# schema.net
KiCad netlist of a schematic drawn in EAGLE
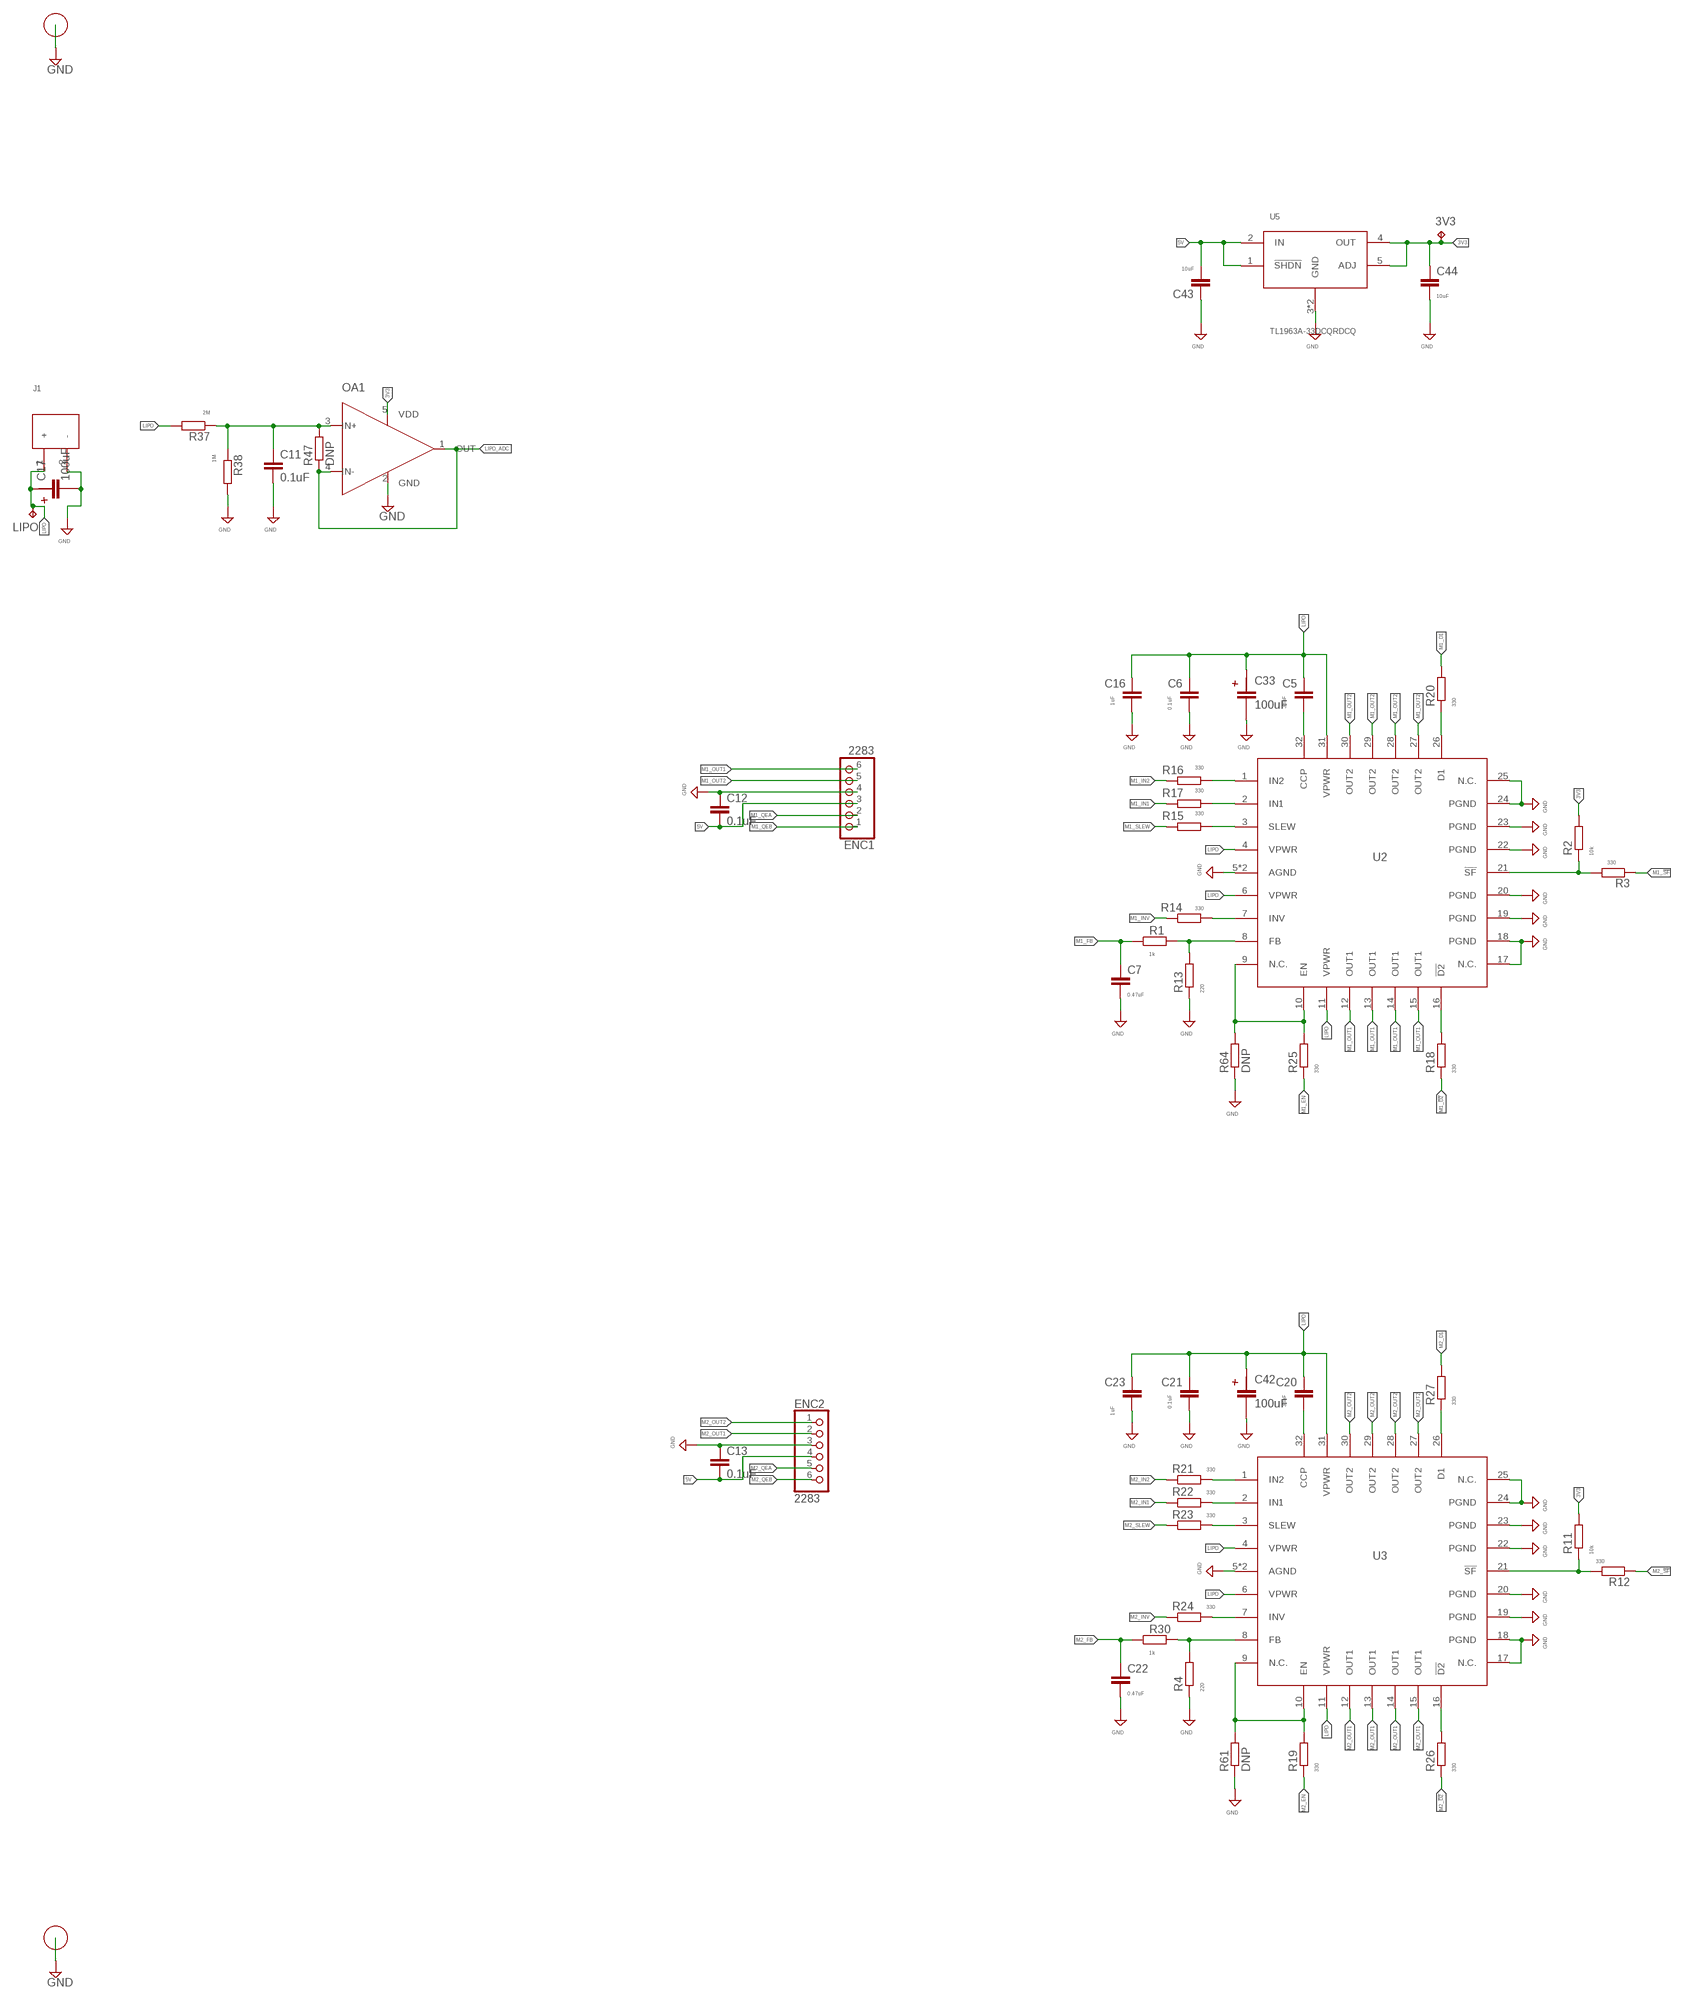
[diagram p0: schematic, sheet 1, part 1 of 2]
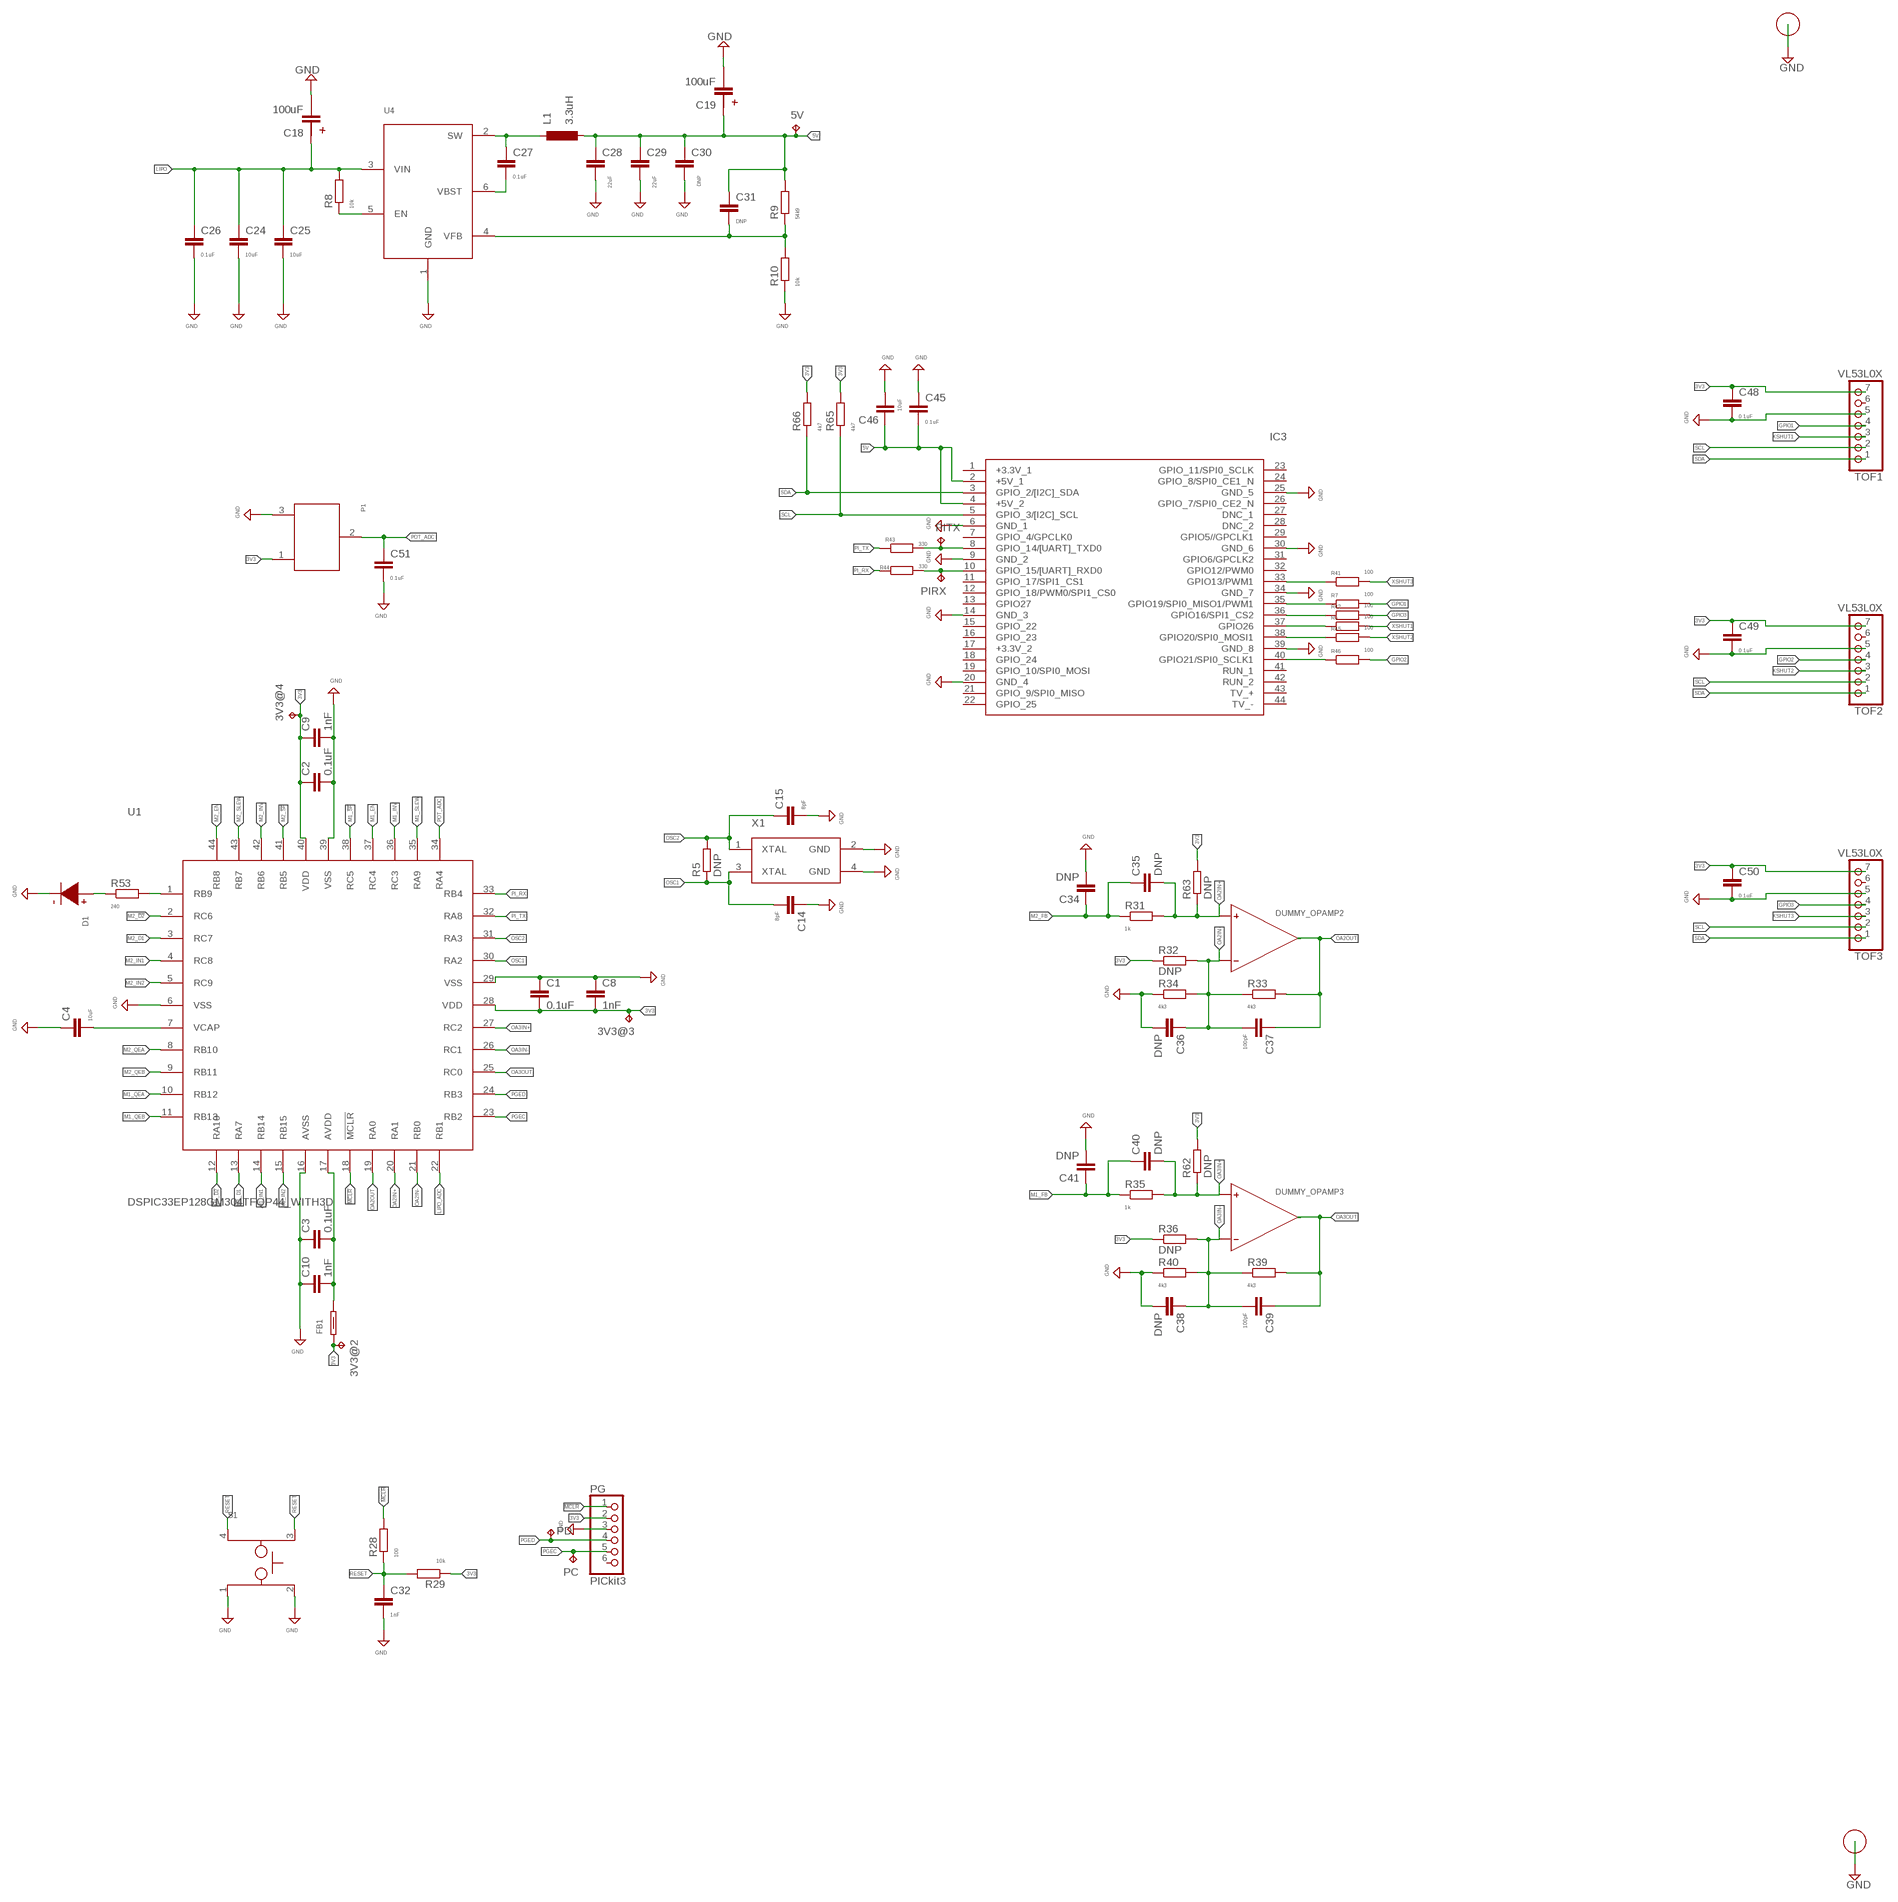
[diagram p1: schematic, sheet 1, part 2 of 2]

(export (version "E")
  (design (tool "Eeschema 10.0.6"))
  (components
    (comp (ref "3V3")
      (value "TPB1,27")
      (footprint "eagle-import:B1,27")
      (libsource (lib "eagle-import") (part "TPB1,27"))
    )
    (comp (ref "3V3@2")
      (value "TPB1,27")
      (footprint "eagle-import:B1,27")
      (libsource (lib "eagle-import") (part "TPB1,27"))
    )
    (comp (ref "3V3@3")
      (value "TPB1,27")
      (footprint "eagle-import:B1,27")
      (libsource (lib "eagle-import") (part "TPB1,27"))
    )
    (comp (ref "3V3@4")
      (value "TPB1,27")
      (footprint "eagle-import:B1,27")
      (libsource (lib "eagle-import") (part "TPB1,27"))
    )
    (comp (ref "5V")
      (value "TPB1,27")
      (footprint "eagle-import:B1,27")
      (libsource (lib "eagle-import") (part "TPB1,27"))
    )
    (comp (ref "C1")
      (value "0.1uF")
      (footprint "eagle-import:C0402K")
      (fields (field (name "MANUFACTURER_PART_NUMBER") "CC0402KRX7R7BB104"))
      (libsource (lib "eagle-import") (part "C-EUC0402K"))
    )
    (comp (ref "C2")
      (value "0.1uF")
      (footprint "eagle-import:C0402K")
      (fields (field (name "MANUFACTURER_PART_NUMBER") "CC0402KRX7R7BB104"))
      (libsource (lib "eagle-import") (part "C-EUC0402K"))
    )
    (comp (ref "C3")
      (value "0.1uF")
      (footprint "eagle-import:C0402K")
      (fields (field (name "MANUFACTURER_PART_NUMBER") "CC0402KRX7R7BB104"))
      (libsource (lib "eagle-import") (part "C-EUC0402K"))
    )
    (comp (ref "C4")
      (value "10uF")
      (footprint "eagle-import:C1210K")
      (fields (field (name "MANUFACTURER_PART_NUMBER") "TAJB106K016TNJ"))
      (libsource (lib "eagle-import") (part "C-EUC1210K"))
    )
    (comp (ref "C5")
      (value "33nF")
      (footprint "eagle-import:C0603K")
      (fields (field (name "MANUFACTURER_PART_NUMBER") "CC0603KRX7R9BB333"))
      (libsource (lib "eagle-import") (part "C-EUC0603K"))
    )
    (comp (ref "C6")
      (value "0.1uF")
      (footprint "eagle-import:C0603K")
      (fields (field (name "MANUFACTURER_PART_NUMBER") "CC0603KRX7R9BB104"))
      (libsource (lib "eagle-import") (part "C-EUC0603K"))
    )
    (comp (ref "C7")
      (value "0.47uF")
      (footprint "eagle-import:C0603K")
      (fields (field (name "MANUFACTURER_PART_NUMBER") "TMK107B7474KA-TR"))
      (libsource (lib "eagle-import") (part "C-EUC0603K"))
    )
    (comp (ref "C8")
      (value "1nF")
      (footprint "eagle-import:C0402K")
      (fields (field (name "MANUFACTURER_PART_NUMBER") "AC0402KRX7R7BB102"))
      (libsource (lib "eagle-import") (part "C-EUC0402K"))
    )
    (comp (ref "C9")
      (value "1nF")
      (footprint "eagle-import:C0402K")
      (fields (field (name "MANUFACTURER_PART_NUMBER") "AC0402KRX7R7BB102"))
      (libsource (lib "eagle-import") (part "C-EUC0402K"))
    )
    (comp (ref "C10")
      (value "1nF")
      (footprint "eagle-import:C0402K")
      (fields (field (name "MANUFACTURER_PART_NUMBER") "AC0402KRX7R7BB102"))
      (libsource (lib "eagle-import") (part "C-EUC0402K"))
    )
    (comp (ref "C11")
      (value "0.1uF")
      (footprint "eagle-import:C0603K")
      (fields (field (name "MANUFACTURER_PART_NUMBER") "CC0603KRX7R9BB104"))
      (libsource (lib "eagle-import") (part "C-EUC0603K"))
    )
    (comp (ref "C12")
      (value "0.1uF")
      (footprint "eagle-import:C0603K")
      (fields (field (name "MANUFACTURER_PART_NUMBER") "CC0603KRX7R9BB104"))
      (libsource (lib "eagle-import") (part "C-EUC0603K"))
    )
    (comp (ref "C13")
      (value "0.1uF")
      (footprint "eagle-import:C0603K")
      (fields (field (name "MANUFACTURER_PART_NUMBER") "CC0603KRX7R9BB104"))
      (libsource (lib "eagle-import") (part "C-EUC0603K"))
    )
    (comp (ref "C14")
      (value "8pF")
      (footprint "eagle-import:C0402K")
      (fields (field (name "MANUFACTURER_PART_NUMBER") "GCM1555C1H8R0DA16D"))
      (libsource (lib "eagle-import") (part "C-EUC0402K"))
    )
    (comp (ref "C15")
      (value "8pF")
      (footprint "eagle-import:C0402K")
      (fields (field (name "MANUFACTURER_PART_NUMBER") "GCM1555C1H8R0DA16D"))
      (libsource (lib "eagle-import") (part "C-EUC0402K"))
    )
    (comp (ref "C16")
      (value "1uF")
      (footprint "eagle-import:C0603K")
      (fields (field (name "MANUFACTURER_PART_NUMBER") "UMK107AB7105KA-T"))
      (libsource (lib "eagle-import") (part "C-EUC0603K"))
    )
    (comp (ref "C17")
      (value "100uF")
      (footprint "eagle-import:CAPMP7141X430")
      (fields (field (name "MANUFACTURER_PART_NUMBER") "T491X107M025AT"))
      (libsource (lib "eagle-import") (part "TANTALUM_2917CASE_X"))
    )
    (comp (ref "C18")
      (value "100uF")
      (footprint "eagle-import:CAPAE660X770")
      (fields (field (name "MANUFACTURER_PART_NUMBER") "865080545012"))
      (libsource (lib "eagle-import") (part "WURTH_CAPWE"))
    )
    (comp (ref "C19")
      (value "100uF")
      (footprint "eagle-import:CAPAE660X770")
      (fields (field (name "MANUFACTURER_PART_NUMBER") "865080545012"))
      (libsource (lib "eagle-import") (part "WURTH_CAPWE"))
    )
    (comp (ref "C20")
      (value "33nF")
      (footprint "eagle-import:C0603K")
      (fields (field (name "MANUFACTURER_PART_NUMBER") "CC0603KRX7R9BB333"))
      (libsource (lib "eagle-import") (part "C-EUC0603K"))
    )
    (comp (ref "C21")
      (value "0.1uF")
      (footprint "eagle-import:C0603K")
      (fields (field (name "MANUFACTURER_PART_NUMBER") "CC0603KRX7R9BB104"))
      (libsource (lib "eagle-import") (part "C-EUC0603K"))
    )
    (comp (ref "C22")
      (value "0.47uF")
      (footprint "eagle-import:C0603K")
      (fields (field (name "MANUFACTURER_PART_NUMBER") "TMK107B7474KA-TR"))
      (libsource (lib "eagle-import") (part "C-EUC0603K"))
    )
    (comp (ref "C23")
      (value "1uF")
      (footprint "eagle-import:C0603K")
      (fields (field (name "MANUFACTURER_PART_NUMBER") "UMK107AB7105KA-T"))
      (libsource (lib "eagle-import") (part "C-EUC0603K"))
    )
    (comp (ref "C24")
      (value "10uF")
      (footprint "eagle-import:C1206K")
      (fields (field (name "MANUFACTURER_PART_NUMBER") "GMK316AB7106KL-TR"))
      (libsource (lib "eagle-import") (part "C-EUC1206K"))
    )
    (comp (ref "C25")
      (value "10uF")
      (footprint "eagle-import:C1206K")
      (fields (field (name "MANUFACTURER_PART_NUMBER") "GMK316AB7106KL-TR"))
      (libsource (lib "eagle-import") (part "C-EUC1206K"))
    )
    (comp (ref "C26")
      (value "0.1uF")
      (footprint "eagle-import:C0603K")
      (fields (field (name "MANUFACTURER_PART_NUMBER") "CC0603KRX7R9BB104"))
      (libsource (lib "eagle-import") (part "C-EUC0603K"))
    )
    (comp (ref "C27")
      (value "0.1uF")
      (footprint "eagle-import:C0603K")
      (fields (field (name "MANUFACTURER_PART_NUMBER") "CC0603KRX7R9BB104"))
      (libsource (lib "eagle-import") (part "C-EUC0603K"))
    )
    (comp (ref "C28")
      (value "22uF")
      (footprint "eagle-import:C1206")
      (fields (field (name "MANUFACTURER_PART_NUMBER") "EMK316BB7226ML-T"))
      (libsource (lib "eagle-import") (part "C-EUC1206"))
    )
    (comp (ref "C29")
      (value "22uF")
      (footprint "eagle-import:C1206")
      (fields (field (name "MANUFACTURER_PART_NUMBER") "EMK316BB7226ML-T"))
      (libsource (lib "eagle-import") (part "C-EUC1206"))
    )
    (comp (ref "C30")
      (value "DNP")
      (footprint "eagle-import:C1206")
      (libsource (lib "eagle-import") (part "C-EUC1206"))
    )
    (comp (ref "C31")
      (value "DNP")
      (footprint "eagle-import:C0603K")
      (libsource (lib "eagle-import") (part "C-EUC0603K"))
    )
    (comp (ref "C32")
      (value "1nF")
      (footprint "eagle-import:C0603K")
      (fields (field (name "MANUFACTURER_PART_NUMBER") "885012206083"))
      (libsource (lib "eagle-import") (part "C-EUC0603K"))
    )
    (comp (ref "C33")
      (value "100uF")
      (footprint "eagle-import:CAPAE660X800")
      (fields (field (name "MANUFACTURER_PART_NUMBER") "EEH-ZA1E101XV"))
      (libsource (lib "eagle-import") (part "EEH-ZA1E101XVCAP_D8"))
    )
    (comp (ref "C34")
      (value "DNP")
      (footprint "eagle-import:C0603K")
      (libsource (lib "eagle-import") (part "C-EUC0603K"))
    )
    (comp (ref "C35")
      (value "DNP")
      (footprint "eagle-import:C0603K")
      (libsource (lib "eagle-import") (part "C-EUC0603K"))
    )
    (comp (ref "C36")
      (value "DNP")
      (footprint "eagle-import:C0603K")
      (libsource (lib "eagle-import") (part "C-EUC0603K"))
    )
    (comp (ref "C37")
      (value "100pF")
      (footprint "eagle-import:C0603K")
      (fields (field (name "MANUFACTURER_PART_NUMBER") "885342206001"))
      (libsource (lib "eagle-import") (part "C-EUC0603K"))
    )
    (comp (ref "C38")
      (value "DNP")
      (footprint "eagle-import:C0603K")
      (libsource (lib "eagle-import") (part "C-EUC0603K"))
    )
    (comp (ref "C39")
      (value "100pF")
      (footprint "eagle-import:C0603K")
      (fields (field (name "MANUFACTURER_PART_NUMBER") "885342206001"))
      (libsource (lib "eagle-import") (part "C-EUC0603K"))
    )
    (comp (ref "C40")
      (value "DNP")
      (footprint "eagle-import:C0603K")
      (libsource (lib "eagle-import") (part "C-EUC0603K"))
    )
    (comp (ref "C41")
      (value "DNP")
      (footprint "eagle-import:C0603K")
      (libsource (lib "eagle-import") (part "C-EUC0603K"))
    )
    (comp (ref "C42")
      (value "100uF")
      (footprint "eagle-import:CAPAE660X800")
      (fields (field (name "MANUFACTURER_PART_NUMBER") "EEH-ZA1E101XV"))
      (libsource (lib "eagle-import") (part "EEH-ZA1E101XVCAP_D8"))
    )
    (comp (ref "C43")
      (value "10uF")
      (footprint "eagle-import:C1210K")
      (fields (field (name "MANUFACTURER_PART_NUMBER") "GRM32DR71E106MA12L"))
      (libsource (lib "eagle-import") (part "C-EUC1210K"))
    )
    (comp (ref "C44")
      (value "10uF")
      (footprint "eagle-import:C1210K")
      (fields (field (name "MANUFACTURER_PART_NUMBER") "GRM32DR71E106MA12L"))
      (libsource (lib "eagle-import") (part "C-EUC1210K"))
    )
    (comp (ref "C45")
      (value "0.1uF")
      (footprint "eagle-import:C0603K")
      (fields (field (name "MANUFACTURER_PART_NUMBER") "CC0603KRX7R9BB104"))
      (libsource (lib "eagle-import") (part "C-EUC0603K"))
    )
    (comp (ref "C46")
      (value "10uF")
      (footprint "eagle-import:C1210K")
      (fields (field (name "MANUFACTURER_PART_NUMBER") "TAJB106K016TNJ"))
      (libsource (lib "eagle-import") (part "C-EUC1210K"))
    )
    (comp (ref "C48")
      (value "0.1uF")
      (footprint "eagle-import:C0603K")
      (fields (field (name "MANUFACTURER_PART_NUMBER") "CC0603KRX7R9BB104"))
      (libsource (lib "eagle-import") (part "C-EUC0603K"))
    )
    (comp (ref "C49")
      (value "0.1uF")
      (footprint "eagle-import:C0603K")
      (fields (field (name "MANUFACTURER_PART_NUMBER") "CC0603KRX7R9BB104"))
      (libsource (lib "eagle-import") (part "C-EUC0603K"))
    )
    (comp (ref "C50")
      (value "0.1uF")
      (footprint "eagle-import:C0603K")
      (fields (field (name "MANUFACTURER_PART_NUMBER") "CC0603KRX7R9BB104"))
      (libsource (lib "eagle-import") (part "C-EUC0603K"))
    )
    (comp (ref "C51")
      (value "0.1uF")
      (footprint "eagle-import:C0603K")
      (fields (field (name "MANUFACTURER_PART_NUMBER") "CC0603KRX7R9BB104"))
      (libsource (lib "eagle-import") (part "C-EUC0603K"))
    )
    (comp (ref "D1")
      (value "LED0805")
      (footprint "eagle-import:LEDC2012X80")
      (fields (field (name "MANUFACTURER_PART_NUMBER") "LTST-C171GKT"))
      (libsource (lib "eagle-import") (part "LED0805"))
    )
    (comp (ref "ENC1")
      (value "2283")
      (footprint "eagle-import:1X06_90")
      (libsource (lib "eagle-import") (part "PINHD-1X6/90"))
    )
    (comp (ref "ENC2")
      (value "2283")
      (footprint "eagle-import:1X06_90")
      (libsource (lib "eagle-import") (part "PINHD-1X6/90"))
    )
    (comp (ref "FB1")
      (value "FERRITE_BEADS0805")
      (footprint "eagle-import:BEADC2012X105")
      (fields (field (name "MANUFACTURER_PART_NUMBER") "MPZ2012S102JTD25"))
      (libsource (lib "eagle-import") (part "FERRITE_BEADS0805"))
    )
    (comp (ref "IC3")
      (value "RASPBERRY_PI_ZERO_W_(V1.3)NO_HOLE")
      (footprint "eagle-import:PI_0_W")
      (libsource (lib "eagle-import") (part "RASPBERRY_PI_ZERO_W_(V1.3)NO_HOLE"))
    )
    (comp (ref "J1")
      (value "XT60")
      (footprint "eagle-import:XT60")
      (fields (field (name "MANUFACTURER_PART_NUMBER") "PRT-10474"))
      (libsource (lib "eagle-import") (part "XT60"))
    )
    (comp (ref "L1")
      (value "3.3uH")
      (footprint "eagle-import:INDDFN700X690X400-2")
      (fields (field (name "MANUFACTURER_PART_NUMBER") "744311330"))
      (libsource (lib "eagle-import") (part "WURTH_INDUCTOR7040"))
    )
    (comp (ref "LIPO")
      (value "TPB1,27")
      (footprint "eagle-import:B1,27")
      (libsource (lib "eagle-import") (part "TPB1,27"))
    )
    (comp (ref "OA1")
      (value "AMPLIFIERSOT25")
      (footprint "eagle-import:SOT95P285X115-5")
      (fields (field (name "MANUFACTURER_PART_NUMBER") "TLV271CW5-7"))
      (libsource (lib "eagle-import") (part "AMPLIFIERSOT25"))
    )
    (comp (ref "P1")
      (value "POTENSIOMETER")
      (footprint "eagle-import:PVG3A")
      (fields (field (name "MANUFACTURER_PART_NUMBER") "PVG3A203C01R00"))
      (libsource (lib "eagle-import") (part "POTENSIOMETER"))
    )
    (comp (ref "PC")
      (value "TPB1,27")
      (footprint "eagle-import:B1,27")
      (libsource (lib "eagle-import") (part "TPB1,27"))
    )
    (comp (ref "PD")
      (value "TPB1,27")
      (footprint "eagle-import:B1,27")
      (libsource (lib "eagle-import") (part "TPB1,27"))
    )
    (comp (ref "PG")
      (value "PICkit3")
      (footprint "eagle-import:1X06")
      (libsource (lib "eagle-import") (part "PINHD-1X6"))
    )
    (comp (ref "PIRX")
      (value "TPB1,27")
      (footprint "eagle-import:B1,27")
      (libsource (lib "eagle-import") (part "TPB1,27"))
    )
    (comp (ref "PITX")
      (value "TPB1,27")
      (footprint "eagle-import:B1,27")
      (libsource (lib "eagle-import") (part "TPB1,27"))
    )
    (comp (ref "R1")
      (value "1k")
      (footprint "eagle-import:R0603")
      (fields (field (name "MANUFACTURER_PART_NUMBER") "ERJ-3RBD102V"))
      (libsource (lib "eagle-import") (part "R-EU_R0603"))
    )
    (comp (ref "R2")
      (value "10k")
      (footprint "eagle-import:R0603")
      (fields (field (name "MANUFACTURER_PART_NUMBER") "ERJ-3RBD1002V"))
      (libsource (lib "eagle-import") (part "R-EU_R0603"))
    )
    (comp (ref "R3")
      (value "330")
      (footprint "eagle-import:R0603")
      (fields (field (name "MANUFACTURER_PART_NUMBER") "RC0603FR-07330RL"))
      (libsource (lib "eagle-import") (part "R-EU_R0603"))
    )
    (comp (ref "R4")
      (value "220")
      (footprint "eagle-import:R0603")
      (fields (field (name "MANUFACTURER_PART_NUMBER") "UCR03EVPFLR220"))
      (libsource (lib "eagle-import") (part "R-EU_R0603"))
    )
    (comp (ref "R5")
      (value "DNP")
      (footprint "eagle-import:R0402")
      (libsource (lib "eagle-import") (part "R-EU_R0402"))
    )
    (comp (ref "R6")
      (value "100")
      (footprint "eagle-import:R0603")
      (fields (field (name "MANUFACTURER_PART_NUMBER") "AC0603FR-13100RL"))
      (libsource (lib "eagle-import") (part "R-EU_R0603"))
    )
    (comp (ref "R7")
      (value "100")
      (footprint "eagle-import:R0603")
      (fields (field (name "MANUFACTURER_PART_NUMBER") "AC0603FR-13100RL"))
      (libsource (lib "eagle-import") (part "R-EU_R0603"))
    )
    (comp (ref "R8")
      (value "10k")
      (footprint "eagle-import:R0603")
      (fields (field (name "MANUFACTURER_PART_NUMBER") "ERJ-3RBD1002V"))
      (libsource (lib "eagle-import") (part "R-EU_R0603"))
    )
    (comp (ref "R9")
      (value "54k9")
      (footprint "eagle-import:R0603")
      (fields (field (name "MANUFACTURER_PART_NUMBER") "ERJ-PB3B5492V"))
      (libsource (lib "eagle-import") (part "R-EU_R0603"))
    )
    (comp (ref "R10")
      (value "10k")
      (footprint "eagle-import:R0603")
      (fields (field (name "MANUFACTURER_PART_NUMBER") "ERJ-3RBD1002V"))
      (libsource (lib "eagle-import") (part "R-EU_R0603"))
    )
    (comp (ref "R11")
      (value "10k")
      (footprint "eagle-import:R0603")
      (fields (field (name "MANUFACTURER_PART_NUMBER") "ERJ-3RBD1002V"))
      (libsource (lib "eagle-import") (part "R-EU_R0603"))
    )
    (comp (ref "R12")
      (value "330")
      (footprint "eagle-import:R0603")
      (fields (field (name "MANUFACTURER_PART_NUMBER") "RC0603FR-07330RL"))
      (libsource (lib "eagle-import") (part "R-EU_R0603"))
    )
    (comp (ref "R13")
      (value "220")
      (footprint "eagle-import:R0603")
      (fields (field (name "MANUFACTURER_PART_NUMBER") "UCR03EVPFLR220"))
      (libsource (lib "eagle-import") (part "R-EU_R0603"))
    )
    (comp (ref "R14")
      (value "330")
      (footprint "eagle-import:R0603")
      (fields (field (name "MANUFACTURER_PART_NUMBER") "RC0603FR-07330RL"))
      (libsource (lib "eagle-import") (part "R-EU_R0603"))
    )
    (comp (ref "R15")
      (value "330")
      (footprint "eagle-import:R0603")
      (fields (field (name "MANUFACTURER_PART_NUMBER") "RC0603FR-07330RL"))
      (libsource (lib "eagle-import") (part "R-EU_R0603"))
    )
    (comp (ref "R16")
      (value "330")
      (footprint "eagle-import:R0603")
      (fields (field (name "MANUFACTURER_PART_NUMBER") "RC0603FR-07330RL"))
      (libsource (lib "eagle-import") (part "R-EU_R0603"))
    )
    (comp (ref "R17")
      (value "330")
      (footprint "eagle-import:R0603")
      (fields (field (name "MANUFACTURER_PART_NUMBER") "RC0603FR-07330RL"))
      (libsource (lib "eagle-import") (part "R-EU_R0603"))
    )
    (comp (ref "R18")
      (value "330")
      (footprint "eagle-import:R0603")
      (fields (field (name "MANUFACTURER_PART_NUMBER") "RC0603FR-07330RL"))
      (libsource (lib "eagle-import") (part "R-EU_R0603"))
    )
    (comp (ref "R19")
      (value "330")
      (footprint "eagle-import:R0603")
      (fields (field (name "MANUFACTURER_PART_NUMBER") "RC0603FR-07330RL"))
      (libsource (lib "eagle-import") (part "R-EU_R0603"))
    )
    (comp (ref "R20")
      (value "330")
      (footprint "eagle-import:R0603")
      (fields (field (name "MANUFACTURER_PART_NUMBER") "RC0603FR-07330RL"))
      (libsource (lib "eagle-import") (part "R-EU_R0603"))
    )
    (comp (ref "R21")
      (value "330")
      (footprint "eagle-import:R0603")
      (fields (field (name "MANUFACTURER_PART_NUMBER") "RC0603FR-07330RL"))
      (libsource (lib "eagle-import") (part "R-EU_R0603"))
    )
    (comp (ref "R22")
      (value "330")
      (footprint "eagle-import:R0603")
      (fields (field (name "MANUFACTURER_PART_NUMBER") "RC0603FR-07330RL"))
      (libsource (lib "eagle-import") (part "R-EU_R0603"))
    )
    (comp (ref "R23")
      (value "330")
      (footprint "eagle-import:R0603")
      (fields (field (name "MANUFACTURER_PART_NUMBER") "RC0603FR-07330RL"))
      (libsource (lib "eagle-import") (part "R-EU_R0603"))
    )
    (comp (ref "R24")
      (value "330")
      (footprint "eagle-import:R0603")
      (fields (field (name "MANUFACTURER_PART_NUMBER") "RC0603FR-07330RL"))
      (libsource (lib "eagle-import") (part "R-EU_R0603"))
    )
    (comp (ref "R25")
      (value "330")
      (footprint "eagle-import:R0603")
      (fields (field (name "MANUFACTURER_PART_NUMBER") "RC0603FR-07330RL"))
      (libsource (lib "eagle-import") (part "R-EU_R0603"))
    )
    (comp (ref "R26")
      (value "330")
      (footprint "eagle-import:R0603")
      (fields (field (name "MANUFACTURER_PART_NUMBER") "RC0603FR-07330RL"))
      (libsource (lib "eagle-import") (part "R-EU_R0603"))
    )
    (comp (ref "R27")
      (value "330")
      (footprint "eagle-import:R0603")
      (fields (field (name "MANUFACTURER_PART_NUMBER") "RC0603FR-07330RL"))
      (libsource (lib "eagle-import") (part "R-EU_R0603"))
    )
    (comp (ref "R28")
      (value "100")
      (footprint "eagle-import:R0603")
      (fields (field (name "MANUFACTURER_PART_NUMBER") "AC0603FR-13100RL"))
      (libsource (lib "eagle-import") (part "R-EU_R0603"))
    )
    (comp (ref "R29")
      (value "10k")
      (footprint "eagle-import:R0603")
      (fields (field (name "MANUFACTURER_PART_NUMBER") "ERJ-3RBD1002V"))
      (libsource (lib "eagle-import") (part "R-EU_R0603"))
    )
    (comp (ref "R30")
      (value "1k")
      (footprint "eagle-import:R0603")
      (fields (field (name "MANUFACTURER_PART_NUMBER") "ERJ-3RBD102V"))
      (libsource (lib "eagle-import") (part "R-EU_R0603"))
    )
    (comp (ref "R31")
      (value "1k")
      (footprint "eagle-import:R0603")
      (fields (field (name "MANUFACTURER_PART_NUMBER") "ERJ-3RBD102V"))
      (libsource (lib "eagle-import") (part "R-EU_R0603"))
    )
    (comp (ref "R32")
      (value "DNP")
      (footprint "eagle-import:R0603")
      (libsource (lib "eagle-import") (part "R-EU_R0603"))
    )
    (comp (ref "R33")
      (value "4k3")
      (footprint "eagle-import:R0603")
      (fields (field (name "MANUFACTURER_PART_NUMBER") "AC0603FR-074K3L"))
      (libsource (lib "eagle-import") (part "R-EU_R0603"))
    )
    (comp (ref "R34")
      (value "4k3")
      (footprint "eagle-import:R0603")
      (fields (field (name "MANUFACTURER_PART_NUMBER") "AC0603FR-074K3L"))
      (libsource (lib "eagle-import") (part "R-EU_R0603"))
    )
    (comp (ref "R35")
      (value "1k")
      (footprint "eagle-import:R0603")
      (fields (field (name "MANUFACTURER_PART_NUMBER") "ERJ-3RBD102V"))
      (libsource (lib "eagle-import") (part "R-EU_R0603"))
    )
    (comp (ref "R36")
      (value "DNP")
      (footprint "eagle-import:R0603")
      (libsource (lib "eagle-import") (part "R-EU_R0603"))
    )
    (comp (ref "R37")
      (value "2M")
      (footprint "eagle-import:R0805")
      (fields (field (name "MANUFACTURER_PART_NUMBER") "ERJ-6RED2003V"))
      (libsource (lib "eagle-import") (part "R-EU_R0805"))
    )
    (comp (ref "R38")
      (value "1M")
      (footprint "eagle-import:R0805")
      (fields (field (name "MANUFACTURER_PART_NUMBER") "AC0805FR-13100KL"))
      (libsource (lib "eagle-import") (part "R-EU_R0805"))
    )
    (comp (ref "R39")
      (value "4k3")
      (footprint "eagle-import:R0603")
      (fields (field (name "MANUFACTURER_PART_NUMBER") "AC0603FR-074K3L"))
      (libsource (lib "eagle-import") (part "R-EU_R0603"))
    )
    (comp (ref "R40")
      (value "4k3")
      (footprint "eagle-import:R0603")
      (fields (field (name "MANUFACTURER_PART_NUMBER") "AC0603FR-074K3L"))
      (libsource (lib "eagle-import") (part "R-EU_R0603"))
    )
    (comp (ref "R41")
      (value "100")
      (footprint "eagle-import:R0603")
      (fields (field (name "MANUFACTURER_PART_NUMBER") "AC0603FR-13100RL"))
      (libsource (lib "eagle-import") (part "R-EU_R0603"))
    )
    (comp (ref "R42")
      (value "100")
      (footprint "eagle-import:R0603")
      (fields (field (name "MANUFACTURER_PART_NUMBER") "AC0603FR-13100RL"))
      (libsource (lib "eagle-import") (part "R-EU_R0603"))
    )
    (comp (ref "R43")
      (value "330")
      (footprint "eagle-import:R0603")
      (fields (field (name "MANUFACTURER_PART_NUMBER") "RC0603FR-07330RL"))
      (libsource (lib "eagle-import") (part "R-EU_R0603"))
    )
    (comp (ref "R44")
      (value "330")
      (footprint "eagle-import:R0603")
      (fields (field (name "MANUFACTURER_PART_NUMBER") "RC0603FR-07330RL"))
      (libsource (lib "eagle-import") (part "R-EU_R0603"))
    )
    (comp (ref "R45")
      (value "100")
      (footprint "eagle-import:R0603")
      (fields (field (name "MANUFACTURER_PART_NUMBER") "AC0603FR-13100RL"))
      (libsource (lib "eagle-import") (part "R-EU_R0603"))
    )
    (comp (ref "R46")
      (value "100")
      (footprint "eagle-import:R0603")
      (fields (field (name "MANUFACTURER_PART_NUMBER") "AC0603FR-13100RL"))
      (libsource (lib "eagle-import") (part "R-EU_R0603"))
    )
    (comp (ref "R47")
      (value "DNP")
      (footprint "eagle-import:R0603")
      (libsource (lib "eagle-import") (part "R-EU_R0603"))
    )
    (comp (ref "R53")
      (value "240")
      (footprint "eagle-import:R0603")
      (fields (field (name "MANUFACTURER_PART_NUMBER") "ERJ-3RBD2400V"))
      (libsource (lib "eagle-import") (part "R-EU_R0603"))
    )
    (comp (ref "R61")
      (value "DNP")
      (footprint "eagle-import:R0603")
      (libsource (lib "eagle-import") (part "R-EU_R0603"))
    )
    (comp (ref "R62")
      (value "DNP")
      (footprint "eagle-import:R0603")
      (libsource (lib "eagle-import") (part "R-EU_R0603"))
    )
    (comp (ref "R63")
      (value "DNP")
      (footprint "eagle-import:R0603")
      (libsource (lib "eagle-import") (part "R-EU_R0603"))
    )
    (comp (ref "R64")
      (value "DNP")
      (footprint "eagle-import:R0603")
      (libsource (lib "eagle-import") (part "R-EU_R0603"))
    )
    (comp (ref "R65")
      (value "4k7")
      (footprint "eagle-import:R0603")
      (fields (field (name "MANUFACTURER_PART_NUMBER") "SFR03EZPF4701"))
      (libsource (lib "eagle-import") (part "R-EU_R0603"))
    )
    (comp (ref "R66")
      (value "4k7")
      (footprint "eagle-import:R0603")
      (fields (field (name "MANUFACTURER_PART_NUMBER") "SFR03EZPF4701"))
      (libsource (lib "eagle-import") (part "R-EU_R0603"))
    )
    (comp (ref "S1")
      (value "BUTON_SPST")
      (footprint "eagle-import:BUTON_SMD")
      (fields (field (name "MANUFACTURER_PART_NUMBER") "LL3301NF065QG"))
      (libsource (lib "eagle-import") (part "BUTON_SPST"))
    )
    (comp (ref "TOF1")
      (value "VL53L0X")
      (footprint "eagle-import:1X07_90")
      (libsource (lib "eagle-import") (part "PINHD-1X7/90"))
    )
    (comp (ref "TOF2")
      (value "VL53L0X")
      (footprint "eagle-import:1X07_90")
      (libsource (lib "eagle-import") (part "PINHD-1X7/90"))
    )
    (comp (ref "TOF3")
      (value "VL53L0X")
      (footprint "eagle-import:1X07_90")
      (libsource (lib "eagle-import") (part "PINHD-1X7/90"))
    )
    (comp (ref "U$1")
      (value "MOUNTING_HOLE")
      (footprint "eagle-import:HOLE_3.5MM")
      (libsource (lib "eagle-import") (part "MOUNTING_HOLE"))
    )
    (comp (ref "U$2")
      (value "MOUNTING_HOLE")
      (footprint "eagle-import:HOLE_3.5MM")
      (libsource (lib "eagle-import") (part "MOUNTING_HOLE"))
    )
    (comp (ref "U$3")
      (value "MOUNTING_HOLE")
      (footprint "eagle-import:HOLE_3.5MM")
      (libsource (lib "eagle-import") (part "MOUNTING_HOLE"))
    )
    (comp (ref "U$4")
      (value "MOUNTING_HOLE")
      (footprint "eagle-import:HOLE_3.5MM")
      (libsource (lib "eagle-import") (part "MOUNTING_HOLE"))
    )
    (comp (ref "U1")
      (value "DSPIC33EP128GM304TFQP44_WITH3D")
      (footprint "eagle-import:QFP80P1200X1200X120-44")
      (fields (field (name "MANUFACTURER_PART_NUMBER") "dsPIC33EP128GM304-E/PT"))
      (libsource (lib "eagle-import") (part "DSPIC33EP128GM304TFQP44_WITH3D"))
    )
    (comp (ref "U2")
      (value "NXP_DRIVER")
      (footprint "eagle-import:QFN80P800X800X220-33N")
      (fields (field (name "MANUFACTURER_PART_NUMBER") "MC33926PNB"))
      (libsource (lib "eagle-import") (part "NXP_DRIVER"))
    )
    (comp (ref "U3")
      (value "NXP_DRIVER")
      (footprint "eagle-import:QFN80P800X800X220-33N")
      (fields (field (name "MANUFACTURER_PART_NUMBER") "MC33926PNB"))
      (libsource (lib "eagle-import") (part "NXP_DRIVER"))
    )
    (comp (ref "U4")
      (value "TPS656201TPS565201")
      (footprint "eagle-import:SOT95P280X110-6")
      (fields (field (name "MANUFACTURER_PART_NUMBER") "TPS565201DDCT"))
      (libsource (lib "eagle-import") (part "TPS656201TPS565201"))
    )
    (comp (ref "U5")
      (value "TL1963A-33DCQRDCQ")
      (footprint "eagle-import:SOT127P706X180-6")
      (fields (field (name "MANUFACTURER_PART_NUMBER") "TL1963A-33DCQR"))
      (libsource (lib "eagle-import") (part "TL1963A-33DCQRDCQ"))
    )
    (comp (ref "X1")
      (value "XTALLECX")
      (footprint "eagle-import:OSCCC250X200X60")
      (fields (field (name "MANUFACTURER_PART_NUMBER") "ECS-120-10-36-AGY-TR"))
      (libsource (lib "eagle-import") (part "XTALLECX"))
    )
  )
  (nets
    (net (code "1") (name "/M1_~{D2}") (class "Default")
      (node (ref "R18") (pin "1") (pinfunction "1_1") (pintype "passive"))
      (node (ref "U1") (pin "12") (pinfunction "RA10_12") (pintype "bidirectional"))
    )
    (net (code "2") (name "/M1_~{SF}") (class "Default")
      (node (ref "R3") (pin "1") (pinfunction "1_1") (pintype "passive"))
      (node (ref "U1") (pin "38") (pinfunction "RC5_38") (pintype "bidirectional"))
    )
    (net (code "3") (name "/M2_~{D2}") (class "Default")
      (node (ref "R26") (pin "1") (pinfunction "1_1") (pintype "passive"))
      (node (ref "U1") (pin "2") (pinfunction "RC6_2") (pintype "bidirectional"))
    )
    (net (code "4") (name "/M2_~{SF}") (class "Default")
      (node (ref "R12") (pin "1") (pinfunction "1_1") (pintype "passive"))
      (node (ref "U1") (pin "41") (pinfunction "RB5_41") (pintype "bidirectional"))
    )
    (net (code "5") (name "/~{MCLR}") (class "Default")
      (node (ref "PG") (pin "1") (pinfunction "1_1") (pintype "passive"))
      (node (ref "R28") (pin "2") (pinfunction "2_2") (pintype "passive"))
      (node (ref "U1") (pin "18") (pinfunction "~{MCLR}_18") (pintype "bidirectional"))
    )
    (net (code "6") (name "3V3") (class "Default")
      (node (ref "3V3") (pin "TP") (pinfunction "TP_TP") (pintype "input"))
      (node (ref "3V3@2") (pin "TP") (pinfunction "TP_TP") (pintype "input"))
      (node (ref "3V3@3") (pin "TP") (pinfunction "TP_TP") (pintype "input"))
      (node (ref "3V3@4") (pin "TP") (pinfunction "TP_TP") (pintype "input"))
      (node (ref "C1") (pin "2") (pinfunction "2_2") (pintype "passive"))
      (node (ref "C2") (pin "1") (pinfunction "1_1") (pintype "passive"))
      (node (ref "C44") (pin "1") (pinfunction "1_1") (pintype "passive"))
      (node (ref "C48") (pin "1") (pinfunction "1_1") (pintype "passive"))
      (node (ref "C49") (pin "1") (pinfunction "1_1") (pintype "passive"))
      (node (ref "C50") (pin "1") (pinfunction "1_1") (pintype "passive"))
      (node (ref "C8") (pin "2") (pinfunction "2_2") (pintype "passive"))
      (node (ref "C9") (pin "1") (pinfunction "1_1") (pintype "passive"))
      (node (ref "FB1") (pin "1") (pinfunction "1_1") (pintype "bidirectional"))
      (node (ref "OA1") (pin "5") (pinfunction "VDD_5") (pintype "bidirectional"))
      (node (ref "P1") (pin "1") (pinfunction "3_1") (pintype "bidirectional"))
      (node (ref "PG") (pin "2") (pinfunction "2_2") (pintype "passive"))
      (node (ref "R11") (pin "2") (pinfunction "2_2") (pintype "passive"))
      (node (ref "R2") (pin "2") (pinfunction "2_2") (pintype "passive"))
      (node (ref "R29") (pin "1") (pinfunction "1_1") (pintype "passive"))
      (node (ref "R32") (pin "1") (pinfunction "1_1") (pintype "passive"))
      (node (ref "R36") (pin "1") (pinfunction "1_1") (pintype "passive"))
      (node (ref "R62") (pin "2") (pinfunction "2_2") (pintype "passive"))
      (node (ref "R63") (pin "2") (pinfunction "2_2") (pintype "passive"))
      (node (ref "R65") (pin "2") (pinfunction "2_2") (pintype "passive"))
      (node (ref "R66") (pin "2") (pinfunction "2_2") (pintype "passive"))
      (node (ref "TOF1") (pin "7") (pinfunction "7_7") (pintype "passive"))
      (node (ref "TOF2") (pin "7") (pinfunction "7_7") (pintype "passive"))
      (node (ref "TOF3") (pin "7") (pinfunction "7_7") (pintype "passive"))
      (node (ref "U1") (pin "28") (pinfunction "VDD_28") (pintype "bidirectional"))
      (node (ref "U1") (pin "40") (pinfunction "VDD_40") (pintype "bidirectional"))
      (node (ref "U5") (pin "4") (pinfunction "OUT_4") (pintype "bidirectional"))
      (node (ref "U5") (pin "5") (pinfunction "ADJ_5") (pintype "bidirectional"))
    )
    (net (code "7") (name "5V") (class "Default")
      (node (ref "5V") (pin "TP") (pinfunction "TP_TP") (pintype "input"))
      (node (ref "C12") (pin "2") (pinfunction "2_2") (pintype "passive"))
      (node (ref "C13") (pin "2") (pinfunction "2_2") (pintype "passive"))
      (node (ref "C19") (pin "1") (pinfunction "POSITIVE_1") (pintype "bidirectional"))
      (node (ref "C28") (pin "1") (pinfunction "1_1") (pintype "passive"))
      (node (ref "C29") (pin "1") (pinfunction "1_1") (pintype "passive"))
      (node (ref "C30") (pin "1") (pinfunction "1_1") (pintype "passive"))
      (node (ref "C31") (pin "1") (pinfunction "1_1") (pintype "passive"))
      (node (ref "C43") (pin "2") (pinfunction "2_2") (pintype "passive"))
      (node (ref "C45") (pin "2") (pinfunction "2_2") (pintype "passive"))
      (node (ref "C46") (pin "1") (pinfunction "1_1") (pintype "passive"))
      (node (ref "ENC1") (pin "3") (pinfunction "3_3") (pintype "passive"))
      (node (ref "ENC2") (pin "4") (pinfunction "4_4") (pintype "passive"))
      (node (ref "IC3") (pin "2") (pinfunction "+5V_1_2") (pintype "bidirectional"))
      (node (ref "IC3") (pin "4") (pinfunction "+5V_2_4") (pintype "bidirectional"))
      (node (ref "L1") (pin "2") (pinfunction "P$2_2") (pintype "bidirectional"))
      (node (ref "R9") (pin "2") (pinfunction "2_2") (pintype "passive"))
      (node (ref "U5") (pin "1") (pinfunction "~{SHDN}_1") (pintype "bidirectional"))
      (node (ref "U5") (pin "2") (pinfunction "IN_2") (pintype "bidirectional"))
    )
    (net (code "8") (name "GND") (class "Default")
      (node (ref "C1") (pin "1") (pinfunction "1_1") (pintype "passive"))
      (node (ref "C10") (pin "1") (pinfunction "1_1") (pintype "passive"))
      (node (ref "C11") (pin "2") (pinfunction "2_2") (pintype "passive"))
      (node (ref "C12") (pin "1") (pinfunction "1_1") (pintype "passive"))
      (node (ref "C13") (pin "1") (pinfunction "1_1") (pintype "passive"))
      (node (ref "C14") (pin "1") (pinfunction "1_1") (pintype "passive"))
      (node (ref "C15") (pin "2") (pinfunction "2_2") (pintype "passive"))
      (node (ref "C16") (pin "2") (pinfunction "2_2") (pintype "passive"))
      (node (ref "C17") (pin "1") (pinfunction "NEGATIVE_1") (pintype "bidirectional"))
      (node (ref "C18") (pin "2") (pinfunction "NEGATIVE_2") (pintype "bidirectional"))
      (node (ref "C19") (pin "2") (pinfunction "NEGATIVE_2") (pintype "bidirectional"))
      (node (ref "C2") (pin "2") (pinfunction "2_2") (pintype "passive"))
      (node (ref "C21") (pin "1") (pinfunction "1_1") (pintype "passive"))
      (node (ref "C22") (pin "2") (pinfunction "2_2") (pintype "passive"))
      (node (ref "C23") (pin "2") (pinfunction "2_2") (pintype "passive"))
      (node (ref "C24") (pin "2") (pinfunction "2_2") (pintype "passive"))
      (node (ref "C25") (pin "2") (pinfunction "2_2") (pintype "passive"))
      (node (ref "C26") (pin "2") (pinfunction "2_2") (pintype "passive"))
      (node (ref "C28") (pin "2") (pinfunction "2_2") (pintype "passive"))
      (node (ref "C29") (pin "2") (pinfunction "2_2") (pintype "passive"))
      (node (ref "C3") (pin "1") (pinfunction "1_1") (pintype "passive"))
      (node (ref "C30") (pin "2") (pinfunction "2_2") (pintype "passive"))
      (node (ref "C32") (pin "2") (pinfunction "2_2") (pintype "passive"))
      (node (ref "C33") (pin "2") (pinfunction "NEGATIVE_2") (pintype "bidirectional"))
      (node (ref "C34") (pin "2") (pinfunction "2_2") (pintype "passive"))
      (node (ref "C36") (pin "2") (pinfunction "2_2") (pintype "passive"))
      (node (ref "C38") (pin "2") (pinfunction "2_2") (pintype "passive"))
      (node (ref "C4") (pin "1") (pinfunction "1_1") (pintype "passive"))
      (node (ref "C41") (pin "2") (pinfunction "2_2") (pintype "passive"))
      (node (ref "C42") (pin "2") (pinfunction "NEGATIVE_2") (pintype "bidirectional"))
      (node (ref "C43") (pin "1") (pinfunction "1_1") (pintype "passive"))
      (node (ref "C44") (pin "2") (pinfunction "2_2") (pintype "passive"))
      (node (ref "C45") (pin "1") (pinfunction "1_1") (pintype "passive"))
      (node (ref "C46") (pin "2") (pinfunction "2_2") (pintype "passive"))
      (node (ref "C48") (pin "2") (pinfunction "2_2") (pintype "passive"))
      (node (ref "C49") (pin "2") (pinfunction "2_2") (pintype "passive"))
      (node (ref "C50") (pin "2") (pinfunction "2_2") (pintype "passive"))
      (node (ref "C51") (pin "2") (pinfunction "2_2") (pintype "passive"))
      (node (ref "C6") (pin "1") (pinfunction "1_1") (pintype "passive"))
      (node (ref "C7") (pin "2") (pinfunction "2_2") (pintype "passive"))
      (node (ref "C8") (pin "1") (pinfunction "1_1") (pintype "passive"))
      (node (ref "C9") (pin "2") (pinfunction "2_2") (pintype "passive"))
      (node (ref "D1") (pin "1") (pinfunction "-_1") (pintype "bidirectional"))
      (node (ref "ENC1") (pin "4") (pinfunction "4_4") (pintype "passive"))
      (node (ref "ENC2") (pin "3") (pinfunction "3_3") (pintype "passive"))
      (node (ref "IC3") (pin "14") (pinfunction "GND_3_14") (pintype "bidirectional"))
      (node (ref "IC3") (pin "20") (pinfunction "GND_4_20") (pintype "bidirectional"))
      (node (ref "IC3") (pin "25") (pinfunction "GND_5_25") (pintype "bidirectional"))
      (node (ref "IC3") (pin "30") (pinfunction "GND_6_30") (pintype "bidirectional"))
      (node (ref "IC3") (pin "34") (pinfunction "GND_7_34") (pintype "bidirectional"))
      (node (ref "IC3") (pin "39") (pinfunction "GND_8_39") (pintype "bidirectional"))
      (node (ref "IC3") (pin "6") (pinfunction "GND_1_6") (pintype "bidirectional"))
      (node (ref "IC3") (pin "9") (pinfunction "GND_2_9") (pintype "bidirectional"))
      (node (ref "J1") (pin "2") (pinfunction "-_2") (pintype "bidirectional"))
      (node (ref "OA1") (pin "2") (pinfunction "GND_2") (pintype "bidirectional"))
      (node (ref "P1") (pin "3") (pinfunction "1_3") (pintype "bidirectional"))
      (node (ref "PG") (pin "3") (pinfunction "3_3") (pintype "passive"))
      (node (ref "R10") (pin "1") (pinfunction "1_1") (pintype "passive"))
      (node (ref "R13") (pin "1") (pinfunction "1_1") (pintype "passive"))
      (node (ref "R34") (pin "1") (pinfunction "1_1") (pintype "passive"))
      (node (ref "R38") (pin "2") (pinfunction "2_2") (pintype "passive"))
      (node (ref "R4") (pin "1") (pinfunction "1_1") (pintype "passive"))
      (node (ref "R40") (pin "1") (pinfunction "1_1") (pintype "passive"))
      (node (ref "R61") (pin "1") (pinfunction "1_1") (pintype "passive"))
      (node (ref "R64") (pin "1") (pinfunction "1_1") (pintype "passive"))
      (node (ref "S1") (pin "1") (pinfunction "1_1") (pintype "bidirectional"))
      (node (ref "S1") (pin "2") (pinfunction "2_2") (pintype "bidirectional"))
      (node (ref "TOF1") (pin "5") (pinfunction "5_5") (pintype "passive"))
      (node (ref "TOF2") (pin "5") (pinfunction "5_5") (pintype "passive"))
      (node (ref "TOF3") (pin "5") (pinfunction "5_5") (pintype "passive"))
      (node (ref "U$1") (pin "P$1") (pinfunction "1_P$1") (pintype "bidirectional"))
      (node (ref "U$2") (pin "P$1") (pinfunction "1_P$1") (pintype "bidirectional"))
      (node (ref "U$3") (pin "P$1") (pinfunction "1_P$1") (pintype "bidirectional"))
      (node (ref "U$4") (pin "P$1") (pinfunction "1_P$1") (pintype "bidirectional"))
      (node (ref "U1") (pin "16") (pinfunction "AVSS_16") (pintype "bidirectional"))
      (node (ref "U1") (pin "29") (pinfunction "VSS_29") (pintype "bidirectional"))
      (node (ref "U1") (pin "39") (pinfunction "VSS_39") (pintype "bidirectional"))
      (node (ref "U1") (pin "6") (pinfunction "VSS_6") (pintype "bidirectional"))
      (node (ref "U2") (pin "17") (pinfunction "N.C._17") (pintype "bidirectional"))
      (node (ref "U2") (pin "18") (pinfunction "PGND_18") (pintype "bidirectional"))
      (node (ref "U2") (pin "19") (pinfunction "PGND_19") (pintype "bidirectional"))
      (node (ref "U2") (pin "20") (pinfunction "PGND_20") (pintype "bidirectional"))
      (node (ref "U2") (pin "22") (pinfunction "PGND_22") (pintype "bidirectional"))
      (node (ref "U2") (pin "23") (pinfunction "PGND_23") (pintype "bidirectional"))
      (node (ref "U2") (pin "24") (pinfunction "PGND_24") (pintype "bidirectional"))
      (node (ref "U2") (pin "25") (pinfunction "N.C._25") (pintype "bidirectional"))
      (node (ref "U2") (pin "33") (pinfunction "AGND_33") (pintype "bidirectional"))
      (node (ref "U2") (pin "5") (pinfunction "AGND_5") (pintype "bidirectional"))
      (node (ref "U3") (pin "17") (pinfunction "N.C._17") (pintype "bidirectional"))
      (node (ref "U3") (pin "18") (pinfunction "PGND_18") (pintype "bidirectional"))
      (node (ref "U3") (pin "19") (pinfunction "PGND_19") (pintype "bidirectional"))
      (node (ref "U3") (pin "20") (pinfunction "PGND_20") (pintype "bidirectional"))
      (node (ref "U3") (pin "22") (pinfunction "PGND_22") (pintype "bidirectional"))
      (node (ref "U3") (pin "23") (pinfunction "PGND_23") (pintype "bidirectional"))
      (node (ref "U3") (pin "24") (pinfunction "PGND_24") (pintype "bidirectional"))
      (node (ref "U3") (pin "25") (pinfunction "N.C._25") (pintype "bidirectional"))
      (node (ref "U3") (pin "33") (pinfunction "AGND_33") (pintype "bidirectional"))
      (node (ref "U3") (pin "5") (pinfunction "AGND_5") (pintype "bidirectional"))
      (node (ref "U4") (pin "1") (pinfunction "GND_1") (pintype "bidirectional"))
      (node (ref "U5") (pin "3") (pinfunction "GND_3") (pintype "bidirectional"))
      (node (ref "U5") (pin "6") (pinfunction "GND_6") (pintype "bidirectional"))
      (node (ref "X1") (pin "2") (pinfunction "GND_2") (pintype "bidirectional"))
      (node (ref "X1") (pin "4") (pinfunction "GND_4") (pintype "bidirectional"))
    )
    (net (code "9") (name "GPIO1") (class "Default")
      (node (ref "R7") (pin "2") (pinfunction "2_2") (pintype "passive"))
      (node (ref "TOF1") (pin "4") (pinfunction "4_4") (pintype "passive"))
    )
    (net (code "10") (name "GPIO2") (class "Default")
      (node (ref "R46") (pin "2") (pinfunction "2_2") (pintype "passive"))
      (node (ref "TOF2") (pin "4") (pinfunction "4_4") (pintype "passive"))
    )
    (net (code "11") (name "GPIO3") (class "Default")
      (node (ref "R42") (pin "2") (pinfunction "2_2") (pintype "passive"))
      (node (ref "TOF3") (pin "4") (pinfunction "4_4") (pintype "passive"))
    )
    (net (code "12") (name "LIPO") (class "Default")
      (node (ref "C16") (pin "1") (pinfunction "1_1") (pintype "passive"))
      (node (ref "C17") (pin "2") (pinfunction "POSITIVE_2") (pintype "bidirectional"))
      (node (ref "C18") (pin "1") (pinfunction "POSITIVE_1") (pintype "bidirectional"))
      (node (ref "C20") (pin "2") (pinfunction "2_2") (pintype "passive"))
      (node (ref "C21") (pin "2") (pinfunction "2_2") (pintype "passive"))
      (node (ref "C23") (pin "1") (pinfunction "1_1") (pintype "passive"))
      (node (ref "C24") (pin "1") (pinfunction "1_1") (pintype "passive"))
      (node (ref "C25") (pin "1") (pinfunction "1_1") (pintype "passive"))
      (node (ref "C26") (pin "1") (pinfunction "1_1") (pintype "passive"))
      (node (ref "C33") (pin "1") (pinfunction "POSITIVE_1") (pintype "bidirectional"))
      (node (ref "C42") (pin "1") (pinfunction "POSITIVE_1") (pintype "bidirectional"))
      (node (ref "C5") (pin "2") (pinfunction "2_2") (pintype "passive"))
      (node (ref "C6") (pin "2") (pinfunction "2_2") (pintype "passive"))
      (node (ref "J1") (pin "1") (pinfunction "+_1") (pintype "bidirectional"))
      (node (ref "LIPO") (pin "TP") (pinfunction "TP_TP") (pintype "input"))
      (node (ref "R37") (pin "2") (pinfunction "2_2") (pintype "passive"))
      (node (ref "R8") (pin "2") (pinfunction "2_2") (pintype "passive"))
      (node (ref "U2") (pin "11") (pinfunction "VPWR_11") (pintype "bidirectional"))
      (node (ref "U2") (pin "31") (pinfunction "VPWR_31") (pintype "bidirectional"))
      (node (ref "U2") (pin "4") (pinfunction "VPWR_4") (pintype "bidirectional"))
      (node (ref "U2") (pin "6") (pinfunction "VPWR_6") (pintype "bidirectional"))
      (node (ref "U3") (pin "11") (pinfunction "VPWR_11") (pintype "bidirectional"))
      (node (ref "U3") (pin "31") (pinfunction "VPWR_31") (pintype "bidirectional"))
      (node (ref "U3") (pin "4") (pinfunction "VPWR_4") (pintype "bidirectional"))
      (node (ref "U3") (pin "6") (pinfunction "VPWR_6") (pintype "bidirectional"))
      (node (ref "U4") (pin "3") (pinfunction "VIN_3") (pintype "bidirectional"))
    )
    (net (code "13") (name "LIPO_ADC") (class "Default")
      (node (ref "OA1") (pin "1") (pinfunction "OUT_1") (pintype "bidirectional"))
      (node (ref "OA1") (pin "4") (pinfunction "IN-_4") (pintype "bidirectional"))
      (node (ref "R47") (pin "1") (pinfunction "1_1") (pintype "passive"))
      (node (ref "U1") (pin "22") (pinfunction "RB1_22") (pintype "bidirectional"))
    )
    (net (code "14") (name "M1_D1") (class "Default")
      (node (ref "R20") (pin "2") (pinfunction "2_2") (pintype "passive"))
      (node (ref "U1") (pin "13") (pinfunction "RA7_13") (pintype "bidirectional"))
    )
    (net (code "15") (name "M1_EN") (class "Default")
      (node (ref "R25") (pin "1") (pinfunction "1_1") (pintype "passive"))
      (node (ref "U1") (pin "37") (pinfunction "RC4_37") (pintype "bidirectional"))
    )
    (net (code "16") (name "M1_FB") (class "Default")
      (node (ref "C40") (pin "1") (pinfunction "1_1") (pintype "passive"))
      (node (ref "C41") (pin "1") (pinfunction "1_1") (pintype "passive"))
      (node (ref "C7") (pin "1") (pinfunction "1_1") (pintype "passive"))
      (node (ref "R1") (pin "1") (pinfunction "1_1") (pintype "passive"))
      (node (ref "R35") (pin "1") (pinfunction "1_1") (pintype "passive"))
    )
    (net (code "17") (name "M1_IN1") (class "Default")
      (node (ref "R17") (pin "2") (pinfunction "2_2") (pintype "passive"))
      (node (ref "U1") (pin "14") (pinfunction "RB14_14") (pintype "bidirectional"))
    )
    (net (code "18") (name "M1_IN2") (class "Default")
      (node (ref "R16") (pin "2") (pinfunction "2_2") (pintype "passive"))
      (node (ref "U1") (pin "15") (pinfunction "RB15_15") (pintype "bidirectional"))
    )
    (net (code "19") (name "M1_INV") (class "Default")
      (node (ref "R14") (pin "1") (pinfunction "1_1") (pintype "passive"))
      (node (ref "U1") (pin "36") (pinfunction "RC3_36") (pintype "bidirectional"))
    )
    (net (code "20") (name "M1_OUT1") (class "Default")
      (node (ref "ENC1") (pin "6") (pinfunction "6_6") (pintype "passive"))
      (node (ref "U2") (pin "12") (pinfunction "OUT1_12") (pintype "bidirectional"))
      (node (ref "U2") (pin "13") (pinfunction "OUT1_13") (pintype "bidirectional"))
      (node (ref "U2") (pin "14") (pinfunction "OUT1_14") (pintype "bidirectional"))
      (node (ref "U2") (pin "15") (pinfunction "OUT1_15") (pintype "bidirectional"))
    )
    (net (code "21") (name "M1_OUT2") (class "Default")
      (node (ref "ENC1") (pin "5") (pinfunction "5_5") (pintype "passive"))
      (node (ref "U2") (pin "27") (pinfunction "OUT2_27") (pintype "bidirectional"))
      (node (ref "U2") (pin "28") (pinfunction "OUT2_28") (pintype "bidirectional"))
      (node (ref "U2") (pin "29") (pinfunction "OUT2_29") (pintype "bidirectional"))
      (node (ref "U2") (pin "30") (pinfunction "OUT2_30") (pintype "bidirectional"))
    )
    (net (code "22") (name "M1_QEA") (class "Default")
      (node (ref "ENC1") (pin "2") (pinfunction "2_2") (pintype "passive"))
      (node (ref "U1") (pin "10") (pinfunction "RB12_10") (pintype "bidirectional"))
    )
    (net (code "23") (name "M1_QEB") (class "Default")
      (node (ref "ENC1") (pin "1") (pinfunction "1_1") (pintype "passive"))
      (node (ref "U1") (pin "11") (pinfunction "RB13_11") (pintype "bidirectional"))
    )
    (net (code "24") (name "M1_SLEW") (class "Default")
      (node (ref "R15") (pin "2") (pinfunction "2_2") (pintype "passive"))
      (node (ref "U1") (pin "35") (pinfunction "RA9_35") (pintype "bidirectional"))
    )
    (net (code "25") (name "M2_D1") (class "Default")
      (node (ref "R27") (pin "2") (pinfunction "2_2") (pintype "passive"))
      (node (ref "U1") (pin "3") (pinfunction "RC7_3") (pintype "bidirectional"))
    )
    (net (code "26") (name "M2_EN") (class "Default")
      (node (ref "R19") (pin "1") (pinfunction "1_1") (pintype "passive"))
      (node (ref "U1") (pin "44") (pinfunction "RB8_44") (pintype "bidirectional"))
    )
    (net (code "27") (name "M2_FB") (class "Default")
      (node (ref "C22") (pin "1") (pinfunction "1_1") (pintype "passive"))
      (node (ref "C34") (pin "1") (pinfunction "1_1") (pintype "passive"))
      (node (ref "C35") (pin "1") (pinfunction "1_1") (pintype "passive"))
      (node (ref "R30") (pin "1") (pinfunction "1_1") (pintype "passive"))
      (node (ref "R31") (pin "1") (pinfunction "1_1") (pintype "passive"))
    )
    (net (code "28") (name "M2_IN1") (class "Default")
      (node (ref "R22") (pin "1") (pinfunction "1_1") (pintype "passive"))
      (node (ref "U1") (pin "4") (pinfunction "RC8_4") (pintype "bidirectional"))
    )
    (net (code "29") (name "M2_IN2") (class "Default")
      (node (ref "R21") (pin "1") (pinfunction "1_1") (pintype "passive"))
      (node (ref "U1") (pin "5") (pinfunction "RC9_5") (pintype "bidirectional"))
    )
    (net (code "30") (name "M2_INV") (class "Default")
      (node (ref "R24") (pin "1") (pinfunction "1_1") (pintype "passive"))
      (node (ref "U1") (pin "42") (pinfunction "RB6_42") (pintype "bidirectional"))
    )
    (net (code "31") (name "M2_OUT1") (class "Default")
      (node (ref "ENC2") (pin "2") (pinfunction "2_2") (pintype "passive"))
      (node (ref "U3") (pin "12") (pinfunction "OUT1_12") (pintype "bidirectional"))
      (node (ref "U3") (pin "13") (pinfunction "OUT1_13") (pintype "bidirectional"))
      (node (ref "U3") (pin "14") (pinfunction "OUT1_14") (pintype "bidirectional"))
      (node (ref "U3") (pin "15") (pinfunction "OUT1_15") (pintype "bidirectional"))
    )
    (net (code "32") (name "M2_OUT2") (class "Default")
      (node (ref "ENC2") (pin "1") (pinfunction "1_1") (pintype "passive"))
      (node (ref "U3") (pin "27") (pinfunction "OUT2_27") (pintype "bidirectional"))
      (node (ref "U3") (pin "28") (pinfunction "OUT2_28") (pintype "bidirectional"))
      (node (ref "U3") (pin "29") (pinfunction "OUT2_29") (pintype "bidirectional"))
      (node (ref "U3") (pin "30") (pinfunction "OUT2_30") (pintype "bidirectional"))
    )
    (net (code "33") (name "M2_QEA") (class "Default")
      (node (ref "ENC2") (pin "5") (pinfunction "5_5") (pintype "passive"))
      (node (ref "U1") (pin "8") (pinfunction "RB10_8") (pintype "bidirectional"))
    )
    (net (code "34") (name "M2_QEB") (class "Default")
      (node (ref "ENC2") (pin "6") (pinfunction "6_6") (pintype "passive"))
      (node (ref "U1") (pin "9") (pinfunction "RB11_9") (pintype "bidirectional"))
    )
    (net (code "35") (name "M2_SLEW") (class "Default")
      (node (ref "R23") (pin "1") (pinfunction "1_1") (pintype "passive"))
      (node (ref "U1") (pin "43") (pinfunction "RB7_43") (pintype "bidirectional"))
    )
    (net (code "36") (name "Net-(D1-+)") (class "Default")
      (node (ref "D1") (pin "2") (pinfunction "+_2") (pintype "bidirectional"))
      (node (ref "R53") (pin "1") (pinfunction "1_1") (pintype "passive"))
    )
    (net (code "37") (name "Net-(IC3-GPIO13{slash}PWM1)") (class "Default")
      (node (ref "IC3") (pin "33") (pinfunction "GPIO13/PWM1_33") (pintype "bidirectional"))
      (node (ref "R41") (pin "1") (pinfunction "1_1") (pintype "passive"))
    )
    (net (code "38") (name "Net-(IC3-GPIO16{slash}SPI1_CS2)") (class "Default")
      (node (ref "IC3") (pin "36") (pinfunction "GPIO16/SPI1_CS2_36") (pintype "bidirectional"))
      (node (ref "R42") (pin "1") (pinfunction "1_1") (pintype "passive"))
    )
    (net (code "39") (name "Net-(IC3-GPIO19{slash}SPI0_MISO1{slash}PWM1)") (class "Default")
      (node (ref "IC3") (pin "35") (pinfunction "GPIO19/SPI0_MISO1/PWM1_35") (pintype "bidirectional"))
      (node (ref "R7") (pin "1") (pinfunction "1_1") (pintype "passive"))
    )
    (net (code "40") (name "Net-(IC3-GPIO20{slash}SPI0_MOSI1)") (class "Default")
      (node (ref "IC3") (pin "38") (pinfunction "GPIO20/SPI0_MOSI1_38") (pintype "bidirectional"))
      (node (ref "R45") (pin "1") (pinfunction "1_1") (pintype "passive"))
    )
    (net (code "41") (name "Net-(IC3-GPIO21{slash}SPI0_SCLK1)") (class "Default")
      (node (ref "IC3") (pin "40") (pinfunction "GPIO21/SPI0_SCLK1_40") (pintype "bidirectional"))
      (node (ref "R46") (pin "1") (pinfunction "1_1") (pintype "passive"))
    )
    (net (code "42") (name "Net-(IC3-GPIO26)") (class "Default")
      (node (ref "IC3") (pin "37") (pinfunction "GPIO26_37") (pintype "bidirectional"))
      (node (ref "R6") (pin "1") (pinfunction "1_1") (pintype "passive"))
    )
    (net (code "43") (name "Net-(IC3-GPIO_14{slash}[UART]_TXD0)") (class "Default")
      (node (ref "IC3") (pin "8") (pinfunction "GPIO_14/[UART]_TXD0_8") (pintype "bidirectional"))
      (node (ref "PITX") (pin "TP") (pinfunction "TP_TP") (pintype "input"))
      (node (ref "R43") (pin "2") (pinfunction "2_2") (pintype "passive"))
    )
    (net (code "44") (name "Net-(IC3-GPIO_15{slash}[UART]_RXD0)") (class "Default")
      (node (ref "IC3") (pin "10") (pinfunction "GPIO_15/[UART]_RXD0_10") (pintype "bidirectional"))
      (node (ref "PIRX") (pin "TP") (pinfunction "TP_TP") (pintype "input"))
      (node (ref "R44") (pin "2") (pinfunction "2_2") (pintype "passive"))
    )
    (net (code "45") (name "Net-(L1-P$1)") (class "Default")
      (node (ref "C27") (pin "1") (pinfunction "1_1") (pintype "passive"))
      (node (ref "L1") (pin "1") (pinfunction "P$1_1") (pintype "bidirectional"))
      (node (ref "U4") (pin "2") (pinfunction "SW_2") (pintype "bidirectional"))
    )
    (net (code "46") (name "Net-(OA1-IN+)") (class "Default")
      (node (ref "C11") (pin "1") (pinfunction "1_1") (pintype "passive"))
      (node (ref "OA1") (pin "3") (pinfunction "IN+_3") (pintype "bidirectional"))
      (node (ref "R37") (pin "1") (pinfunction "1_1") (pintype "passive"))
      (node (ref "R38") (pin "1") (pinfunction "1_1") (pintype "passive"))
      (node (ref "R47") (pin "2") (pinfunction "2_2") (pintype "passive"))
    )
    (net (code "47") (name "Net-(U1-AVDD)") (class "Default")
      (node (ref "C10") (pin "2") (pinfunction "2_2") (pintype "passive"))
      (node (ref "C3") (pin "2") (pinfunction "2_2") (pintype "passive"))
      (node (ref "FB1") (pin "2") (pinfunction "2_2") (pintype "bidirectional"))
      (node (ref "U1") (pin "17") (pinfunction "AVDD_17") (pintype "bidirectional"))
    )
    (net (code "48") (name "Net-(U1-RB9)") (class "Default")
      (node (ref "R53") (pin "2") (pinfunction "2_2") (pintype "passive"))
      (node (ref "U1") (pin "1") (pinfunction "RB9_1") (pintype "bidirectional"))
    )
    (net (code "49") (name "Net-(U1-VCAP)") (class "Default")
      (node (ref "C4") (pin "2") (pinfunction "2_2") (pintype "passive"))
      (node (ref "U1") (pin "7") (pinfunction "VCAP_7") (pintype "bidirectional"))
    )
    (net (code "50") (name "Net-(U2-CCP)") (class "Default")
      (node (ref "C5") (pin "1") (pinfunction "1_1") (pintype "passive"))
      (node (ref "U2") (pin "32") (pinfunction "CCP_32") (pintype "bidirectional"))
    )
    (net (code "51") (name "Net-(U2-D1)") (class "Default")
      (node (ref "R20") (pin "1") (pinfunction "1_1") (pintype "passive"))
      (node (ref "U2") (pin "26") (pinfunction "D1_26") (pintype "bidirectional"))
    )
    (net (code "52") (name "Net-(U2-EN)") (class "Default")
      (node (ref "R25") (pin "2") (pinfunction "2_2") (pintype "passive"))
      (node (ref "R64") (pin "2") (pinfunction "2_2") (pintype "passive"))
      (node (ref "U2") (pin "10") (pinfunction "EN_10") (pintype "bidirectional"))
      (node (ref "U2") (pin "9") (pinfunction "N.C._9") (pintype "bidirectional"))
    )
    (net (code "53") (name "Net-(U2-FB)") (class "Default")
      (node (ref "R1") (pin "2") (pinfunction "2_2") (pintype "passive"))
      (node (ref "R13") (pin "2") (pinfunction "2_2") (pintype "passive"))
      (node (ref "U2") (pin "8") (pinfunction "FB_8") (pintype "bidirectional"))
    )
    (net (code "54") (name "Net-(U2-IN1)") (class "Default")
      (node (ref "R17") (pin "1") (pinfunction "1_1") (pintype "passive"))
      (node (ref "U2") (pin "2") (pinfunction "IN1_2") (pintype "bidirectional"))
    )
    (net (code "55") (name "Net-(U2-IN2)") (class "Default")
      (node (ref "R16") (pin "1") (pinfunction "1_1") (pintype "passive"))
      (node (ref "U2") (pin "1") (pinfunction "IN2_1") (pintype "bidirectional"))
    )
    (net (code "56") (name "Net-(U2-INV)") (class "Default")
      (node (ref "R14") (pin "2") (pinfunction "2_2") (pintype "passive"))
      (node (ref "U2") (pin "7") (pinfunction "INV_7") (pintype "bidirectional"))
    )
    (net (code "57") (name "Net-(U2-SLEW)") (class "Default")
      (node (ref "R15") (pin "1") (pinfunction "1_1") (pintype "passive"))
      (node (ref "U2") (pin "3") (pinfunction "SLEW_3") (pintype "bidirectional"))
    )
    (net (code "58") (name "Net-(U2-~{D2})") (class "Default")
      (node (ref "R18") (pin "2") (pinfunction "2_2") (pintype "passive"))
      (node (ref "U2") (pin "16") (pinfunction "~{D2}_16") (pintype "bidirectional"))
    )
    (net (code "59") (name "Net-(U2-~{SF})") (class "Default")
      (node (ref "R2") (pin "1") (pinfunction "1_1") (pintype "passive"))
      (node (ref "R3") (pin "2") (pinfunction "2_2") (pintype "passive"))
      (node (ref "U2") (pin "21") (pinfunction "~{SF}_21") (pintype "bidirectional"))
    )
    (net (code "60") (name "Net-(U3-CCP)") (class "Default")
      (node (ref "C20") (pin "1") (pinfunction "1_1") (pintype "passive"))
      (node (ref "U3") (pin "32") (pinfunction "CCP_32") (pintype "bidirectional"))
    )
    (net (code "61") (name "Net-(U3-D1)") (class "Default")
      (node (ref "R27") (pin "1") (pinfunction "1_1") (pintype "passive"))
      (node (ref "U3") (pin "26") (pinfunction "D1_26") (pintype "bidirectional"))
    )
    (net (code "62") (name "Net-(U3-EN)") (class "Default")
      (node (ref "R19") (pin "2") (pinfunction "2_2") (pintype "passive"))
      (node (ref "R61") (pin "2") (pinfunction "2_2") (pintype "passive"))
      (node (ref "U3") (pin "10") (pinfunction "EN_10") (pintype "bidirectional"))
      (node (ref "U3") (pin "9") (pinfunction "N.C._9") (pintype "bidirectional"))
    )
    (net (code "63") (name "Net-(U3-FB)") (class "Default")
      (node (ref "R30") (pin "2") (pinfunction "2_2") (pintype "passive"))
      (node (ref "R4") (pin "2") (pinfunction "2_2") (pintype "passive"))
      (node (ref "U3") (pin "8") (pinfunction "FB_8") (pintype "bidirectional"))
    )
    (net (code "64") (name "Net-(U3-IN1)") (class "Default")
      (node (ref "R22") (pin "2") (pinfunction "2_2") (pintype "passive"))
      (node (ref "U3") (pin "2") (pinfunction "IN1_2") (pintype "bidirectional"))
    )
    (net (code "65") (name "Net-(U3-IN2)") (class "Default")
      (node (ref "R21") (pin "2") (pinfunction "2_2") (pintype "passive"))
      (node (ref "U3") (pin "1") (pinfunction "IN2_1") (pintype "bidirectional"))
    )
    (net (code "66") (name "Net-(U3-INV)") (class "Default")
      (node (ref "R24") (pin "2") (pinfunction "2_2") (pintype "passive"))
      (node (ref "U3") (pin "7") (pinfunction "INV_7") (pintype "bidirectional"))
    )
    (net (code "67") (name "Net-(U3-SLEW)") (class "Default")
      (node (ref "R23") (pin "2") (pinfunction "2_2") (pintype "passive"))
      (node (ref "U3") (pin "3") (pinfunction "SLEW_3") (pintype "bidirectional"))
    )
    (net (code "68") (name "Net-(U3-~{D2})") (class "Default")
      (node (ref "R26") (pin "2") (pinfunction "2_2") (pintype "passive"))
      (node (ref "U3") (pin "16") (pinfunction "~{D2}_16") (pintype "bidirectional"))
    )
    (net (code "69") (name "Net-(U3-~{SF})") (class "Default")
      (node (ref "R11") (pin "1") (pinfunction "1_1") (pintype "passive"))
      (node (ref "R12") (pin "2") (pinfunction "2_2") (pintype "passive"))
      (node (ref "U3") (pin "21") (pinfunction "~{SF}_21") (pintype "bidirectional"))
    )
    (net (code "70") (name "Net-(U4-EN)") (class "Default")
      (node (ref "R8") (pin "1") (pinfunction "1_1") (pintype "passive"))
      (node (ref "U4") (pin "5") (pinfunction "EN_5") (pintype "bidirectional"))
    )
    (net (code "71") (name "Net-(U4-VBST)") (class "Default")
      (node (ref "C27") (pin "2") (pinfunction "2_2") (pintype "passive"))
      (node (ref "U4") (pin "6") (pinfunction "VBST_6") (pintype "bidirectional"))
    )
    (net (code "72") (name "Net-(U4-VFB)") (class "Default")
      (node (ref "C31") (pin "2") (pinfunction "2_2") (pintype "passive"))
      (node (ref "R10") (pin "2") (pinfunction "2_2") (pintype "passive"))
      (node (ref "R9") (pin "1") (pinfunction "1_1") (pintype "passive"))
      (node (ref "U4") (pin "4") (pinfunction "VFB_4") (pintype "bidirectional"))
    )
    (net (code "73") (name "OA2IN+") (class "Default")
      (node (ref "C35") (pin "2") (pinfunction "2_2") (pintype "passive"))
      (node (ref "R31") (pin "2") (pinfunction "2_2") (pintype "passive"))
      (node (ref "R63") (pin "1") (pinfunction "1_1") (pintype "passive"))
      (node (ref "U1") (pin "20") (pinfunction "RA1_20") (pintype "bidirectional"))
    )
    (net (code "74") (name "OA2IN-") (class "Default")
      (node (ref "C36") (pin "1") (pinfunction "1_1") (pintype "passive"))
      (node (ref "C37") (pin "2") (pinfunction "2_2") (pintype "passive"))
      (node (ref "R32") (pin "2") (pinfunction "2_2") (pintype "passive"))
      (node (ref "R33") (pin "1") (pinfunction "1_1") (pintype "passive"))
      (node (ref "R34") (pin "2") (pinfunction "2_2") (pintype "passive"))
      (node (ref "U1") (pin "21") (pinfunction "RB0_21") (pintype "bidirectional"))
    )
    (net (code "75") (name "OA2OUT") (class "Default")
      (node (ref "C37") (pin "1") (pinfunction "1_1") (pintype "passive"))
      (node (ref "R33") (pin "2") (pinfunction "2_2") (pintype "passive"))
      (node (ref "U1") (pin "19") (pinfunction "RA0_19") (pintype "bidirectional"))
    )
    (net (code "76") (name "OA3IN+") (class "Default")
      (node (ref "C40") (pin "2") (pinfunction "2_2") (pintype "passive"))
      (node (ref "R35") (pin "2") (pinfunction "2_2") (pintype "passive"))
      (node (ref "R62") (pin "1") (pinfunction "1_1") (pintype "passive"))
      (node (ref "U1") (pin "27") (pinfunction "RC2_27") (pintype "bidirectional"))
    )
    (net (code "77") (name "OA3IN-") (class "Default")
      (node (ref "C38") (pin "1") (pinfunction "1_1") (pintype "passive"))
      (node (ref "C39") (pin "2") (pinfunction "2_2") (pintype "passive"))
      (node (ref "R36") (pin "2") (pinfunction "2_2") (pintype "passive"))
      (node (ref "R39") (pin "1") (pinfunction "1_1") (pintype "passive"))
      (node (ref "R40") (pin "2") (pinfunction "2_2") (pintype "passive"))
      (node (ref "U1") (pin "26") (pinfunction "RC1_26") (pintype "bidirectional"))
    )
    (net (code "78") (name "OA3OUT") (class "Default")
      (node (ref "C39") (pin "1") (pinfunction "1_1") (pintype "passive"))
      (node (ref "R39") (pin "2") (pinfunction "2_2") (pintype "passive"))
      (node (ref "U1") (pin "25") (pinfunction "RC0_25") (pintype "bidirectional"))
    )
    (net (code "79") (name "OSC1") (class "Default")
      (node (ref "C14") (pin "2") (pinfunction "2_2") (pintype "passive"))
      (node (ref "R5") (pin "1") (pinfunction "1_1") (pintype "passive"))
      (node (ref "U1") (pin "30") (pinfunction "RA2_30") (pintype "bidirectional"))
      (node (ref "X1") (pin "3") (pinfunction "XTAL_3") (pintype "bidirectional"))
    )
    (net (code "80") (name "OSC2") (class "Default")
      (node (ref "C15") (pin "1") (pinfunction "1_1") (pintype "passive"))
      (node (ref "R5") (pin "2") (pinfunction "2_2") (pintype "passive"))
      (node (ref "U1") (pin "31") (pinfunction "RA3_31") (pintype "bidirectional"))
      (node (ref "X1") (pin "1") (pinfunction "XTAL_1") (pintype "bidirectional"))
    )
    (net (code "81") (name "PGEC") (class "Default")
      (node (ref "PC") (pin "TP") (pinfunction "TP_TP") (pintype "input"))
      (node (ref "PG") (pin "5") (pinfunction "5_5") (pintype "passive"))
      (node (ref "U1") (pin "23") (pinfunction "RB2_23") (pintype "bidirectional"))
    )
    (net (code "82") (name "PGED") (class "Default")
      (node (ref "PD") (pin "TP") (pinfunction "TP_TP") (pintype "input"))
      (node (ref "PG") (pin "4") (pinfunction "4_4") (pintype "passive"))
      (node (ref "U1") (pin "24") (pinfunction "RB3_24") (pintype "bidirectional"))
    )
    (net (code "83") (name "PI_RX") (class "Default")
      (node (ref "R44") (pin "1") (pinfunction "1_1") (pintype "passive"))
      (node (ref "U1") (pin "33") (pinfunction "RB4_33") (pintype "bidirectional"))
    )
    (net (code "84") (name "PI_TX") (class "Default")
      (node (ref "R43") (pin "1") (pinfunction "1_1") (pintype "passive"))
      (node (ref "U1") (pin "32") (pinfunction "RA8_32") (pintype "bidirectional"))
    )
    (net (code "85") (name "POT_ADC") (class "Default")
      (node (ref "C51") (pin "1") (pinfunction "1_1") (pintype "passive"))
      (node (ref "P1") (pin "2") (pinfunction "2_2") (pintype "bidirectional"))
      (node (ref "U1") (pin "34") (pinfunction "RA4_34") (pintype "bidirectional"))
    )
    (net (code "86") (name "RESET") (class "Default")
      (node (ref "C32") (pin "1") (pinfunction "1_1") (pintype "passive"))
      (node (ref "R28") (pin "1") (pinfunction "1_1") (pintype "passive"))
      (node (ref "R29") (pin "2") (pinfunction "2_2") (pintype "passive"))
      (node (ref "S1") (pin "3") (pinfunction "3_3") (pintype "bidirectional"))
      (node (ref "S1") (pin "4") (pinfunction "4_4") (pintype "bidirectional"))
    )
    (net (code "87") (name "SCL") (class "Default")
      (node (ref "IC3") (pin "5") (pinfunction "GPIO_3/[I2C]_SCL_5") (pintype "bidirectional"))
      (node (ref "R65") (pin "1") (pinfunction "1_1") (pintype "passive"))
      (node (ref "TOF1") (pin "2") (pinfunction "2_2") (pintype "passive"))
      (node (ref "TOF2") (pin "2") (pinfunction "2_2") (pintype "passive"))
      (node (ref "TOF3") (pin "2") (pinfunction "2_2") (pintype "passive"))
    )
    (net (code "88") (name "SDA") (class "Default")
      (node (ref "IC3") (pin "3") (pinfunction "GPIO_2/[I2C]_SDA_3") (pintype "bidirectional"))
      (node (ref "R66") (pin "1") (pinfunction "1_1") (pintype "passive"))
      (node (ref "TOF1") (pin "1") (pinfunction "1_1") (pintype "passive"))
      (node (ref "TOF2") (pin "1") (pinfunction "1_1") (pintype "passive"))
      (node (ref "TOF3") (pin "1") (pinfunction "1_1") (pintype "passive"))
    )
    (net (code "89") (name "XSHUT1") (class "Default")
      (node (ref "R6") (pin "2") (pinfunction "2_2") (pintype "passive"))
      (node (ref "TOF1") (pin "3") (pinfunction "3_3") (pintype "passive"))
    )
    (net (code "90") (name "XSHUT2") (class "Default")
      (node (ref "R45") (pin "2") (pinfunction "2_2") (pintype "passive"))
      (node (ref "TOF2") (pin "3") (pinfunction "3_3") (pintype "passive"))
    )
    (net (code "91") (name "XSHUT3") (class "Default")
      (node (ref "R41") (pin "2") (pinfunction "2_2") (pintype "passive"))
      (node (ref "TOF3") (pin "3") (pinfunction "3_3") (pintype "passive"))
    )
    (net (code "92") (name "unconnected-(IC3-+3.3V_1-Pad1)") (class "Default")
      (node (ref "IC3") (pin "1") (pinfunction "+3.3V_1_1") (pintype "bidirectional"))
    )
    (net (code "93") (name "unconnected-(IC3-+3.3V_2-Pad17)") (class "Default")
      (node (ref "IC3") (pin "17") (pinfunction "+3.3V_2_17") (pintype "bidirectional"))
    )
    (net (code "94") (name "unconnected-(IC3-DNC_1-Pad27)") (class "Default")
      (node (ref "IC3") (pin "27") (pinfunction "DNC_1_27") (pintype "bidirectional"))
    )
    (net (code "95") (name "unconnected-(IC3-DNC_2-Pad28)") (class "Default")
      (node (ref "IC3") (pin "28") (pinfunction "DNC_2_28") (pintype "bidirectional"))
    )
    (net (code "96") (name "unconnected-(IC3-GPIO5{slash}{slash}GPCLK1-Pad29)") (class "Default")
      (node (ref "IC3") (pin "29") (pinfunction "GPIO5//GPCLK1_29") (pintype "bidirectional"))
    )
    (net (code "97") (name "unconnected-(IC3-GPIO6{slash}GPCLK2-Pad31)") (class "Default")
      (node (ref "IC3") (pin "31") (pinfunction "GPIO6/GPCLK2_31") (pintype "bidirectional"))
    )
    (net (code "98") (name "unconnected-(IC3-GPIO12{slash}PWM0-Pad32)") (class "Default")
      (node (ref "IC3") (pin "32") (pinfunction "GPIO12/PWM0_32") (pintype "bidirectional"))
    )
    (net (code "99") (name "unconnected-(IC3-GPIO27-Pad13)") (class "Default")
      (node (ref "IC3") (pin "13") (pinfunction "GPIO27_13") (pintype "bidirectional"))
    )
    (net (code "100") (name "unconnected-(IC3-GPIO_4{slash}GPCLK0-Pad7)") (class "Default")
      (node (ref "IC3") (pin "7") (pinfunction "GPIO_4/GPCLK0_7") (pintype "bidirectional"))
    )
    (net (code "101") (name "unconnected-(IC3-GPIO_7{slash}SPI0_CE2_N-Pad26)") (class "Default")
      (node (ref "IC3") (pin "26") (pinfunction "GPIO_7/SPI0_CE2_N_26") (pintype "bidirectional"))
    )
    (net (code "102") (name "unconnected-(IC3-GPIO_8{slash}SPI0_CE1_N-Pad24)") (class "Default")
      (node (ref "IC3") (pin "24") (pinfunction "GPIO_8/SPI0_CE1_N_24") (pintype "bidirectional"))
    )
    (net (code "103") (name "unconnected-(IC3-GPIO_9{slash}SPI0_MISO-Pad21)") (class "Default")
      (node (ref "IC3") (pin "21") (pinfunction "GPIO_9/SPI0_MISO_21") (pintype "bidirectional"))
    )
    (net (code "104") (name "unconnected-(IC3-GPIO_10{slash}SPI0_MOSI-Pad19)") (class "Default")
      (node (ref "IC3") (pin "19") (pinfunction "GPIO_10/SPI0_MOSI_19") (pintype "bidirectional"))
    )
    (net (code "105") (name "unconnected-(IC3-GPIO_11{slash}SPI0_SCLK-Pad23)") (class "Default")
      (node (ref "IC3") (pin "23") (pinfunction "GPIO_11/SPI0_SCLK_23") (pintype "bidirectional"))
    )
    (net (code "106") (name "unconnected-(IC3-GPIO_17{slash}SPI1_CS1-Pad11)") (class "Default")
      (node (ref "IC3") (pin "11") (pinfunction "GPIO_17/SPI1_CS1_11") (pintype "bidirectional"))
    )
    (net (code "107") (name "unconnected-(IC3-GPIO_18{slash}PWM0{slash}SPI1_CS0-Pad12)") (class "Default")
      (node (ref "IC3") (pin "12") (pinfunction "GPIO_18/PWM0/SPI1_CS0_12") (pintype "bidirectional"))
    )
    (net (code "108") (name "unconnected-(IC3-GPIO_22-Pad15)") (class "Default")
      (node (ref "IC3") (pin "15") (pinfunction "GPIO_22_15") (pintype "bidirectional"))
    )
    (net (code "109") (name "unconnected-(IC3-GPIO_23-Pad16)") (class "Default")
      (node (ref "IC3") (pin "16") (pinfunction "GPIO_23_16") (pintype "bidirectional"))
    )
    (net (code "110") (name "unconnected-(IC3-GPIO_24-Pad18)") (class "Default")
      (node (ref "IC3") (pin "18") (pinfunction "GPIO_24_18") (pintype "bidirectional"))
    )
    (net (code "111") (name "unconnected-(IC3-GPIO_25-Pad22)") (class "Default")
      (node (ref "IC3") (pin "22") (pinfunction "GPIO_25_22") (pintype "bidirectional"))
    )
    (net (code "112") (name "unconnected-(IC3-RUN_1-Pad41)") (class "Default")
      (node (ref "IC3") (pin "41") (pinfunction "RUN_1_41") (pintype "bidirectional"))
    )
    (net (code "113") (name "unconnected-(IC3-RUN_2-Pad42)") (class "Default")
      (node (ref "IC3") (pin "42") (pinfunction "RUN_2_42") (pintype "bidirectional"))
    )
    (net (code "114") (name "unconnected-(IC3-TV_+-Pad43)") (class "Default")
      (node (ref "IC3") (pin "43") (pinfunction "TV_+_43") (pintype "bidirectional"))
    )
    (net (code "115") (name "unconnected-(IC3-TV_--Pad44)") (class "Default")
      (node (ref "IC3") (pin "44") (pinfunction "TV_-_44") (pintype "bidirectional"))
    )
    (net (code "116") (name "unconnected-(PG-Pad6)") (class "Default")
      (node (ref "PG") (pin "6") (pinfunction "6_6") (pintype "passive"))
    )
    (net (code "117") (name "unconnected-(TOF1-Pad6)") (class "Default")
      (node (ref "TOF1") (pin "6") (pinfunction "6_6") (pintype "passive"))
    )
    (net (code "118") (name "unconnected-(TOF2-Pad6)") (class "Default")
      (node (ref "TOF2") (pin "6") (pinfunction "6_6") (pintype "passive"))
    )
    (net (code "119") (name "unconnected-(TOF3-Pad6)") (class "Default")
      (node (ref "TOF3") (pin "6") (pinfunction "6_6") (pintype "passive"))
    )
  )
)
